# xmosio2.net
KiCad netlist of a schematic drawn in EAGLE
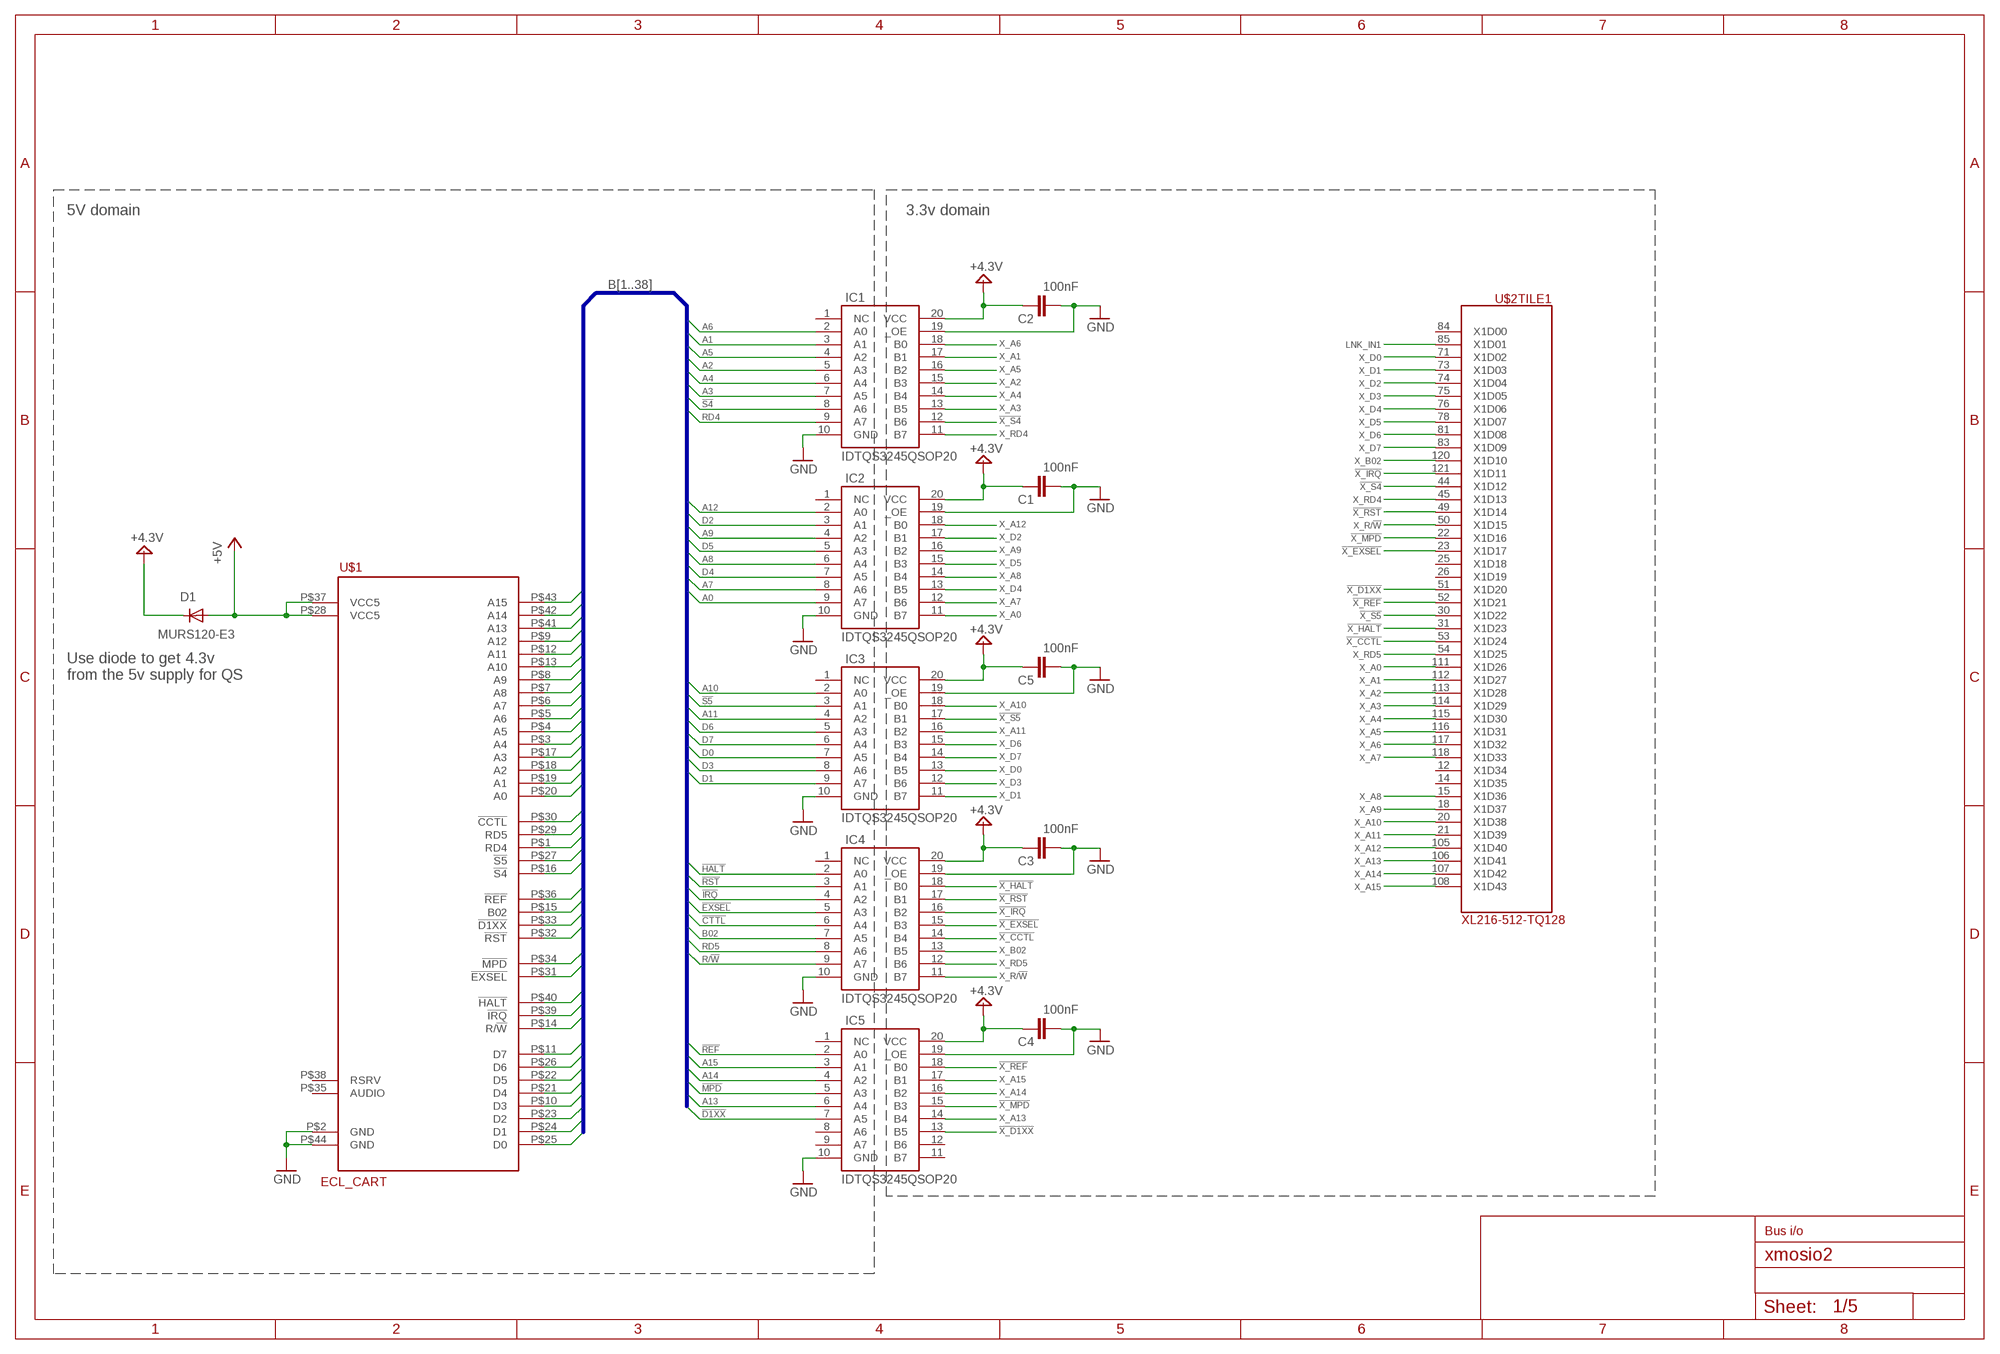
[diagram p0: schematic, sheet 1]
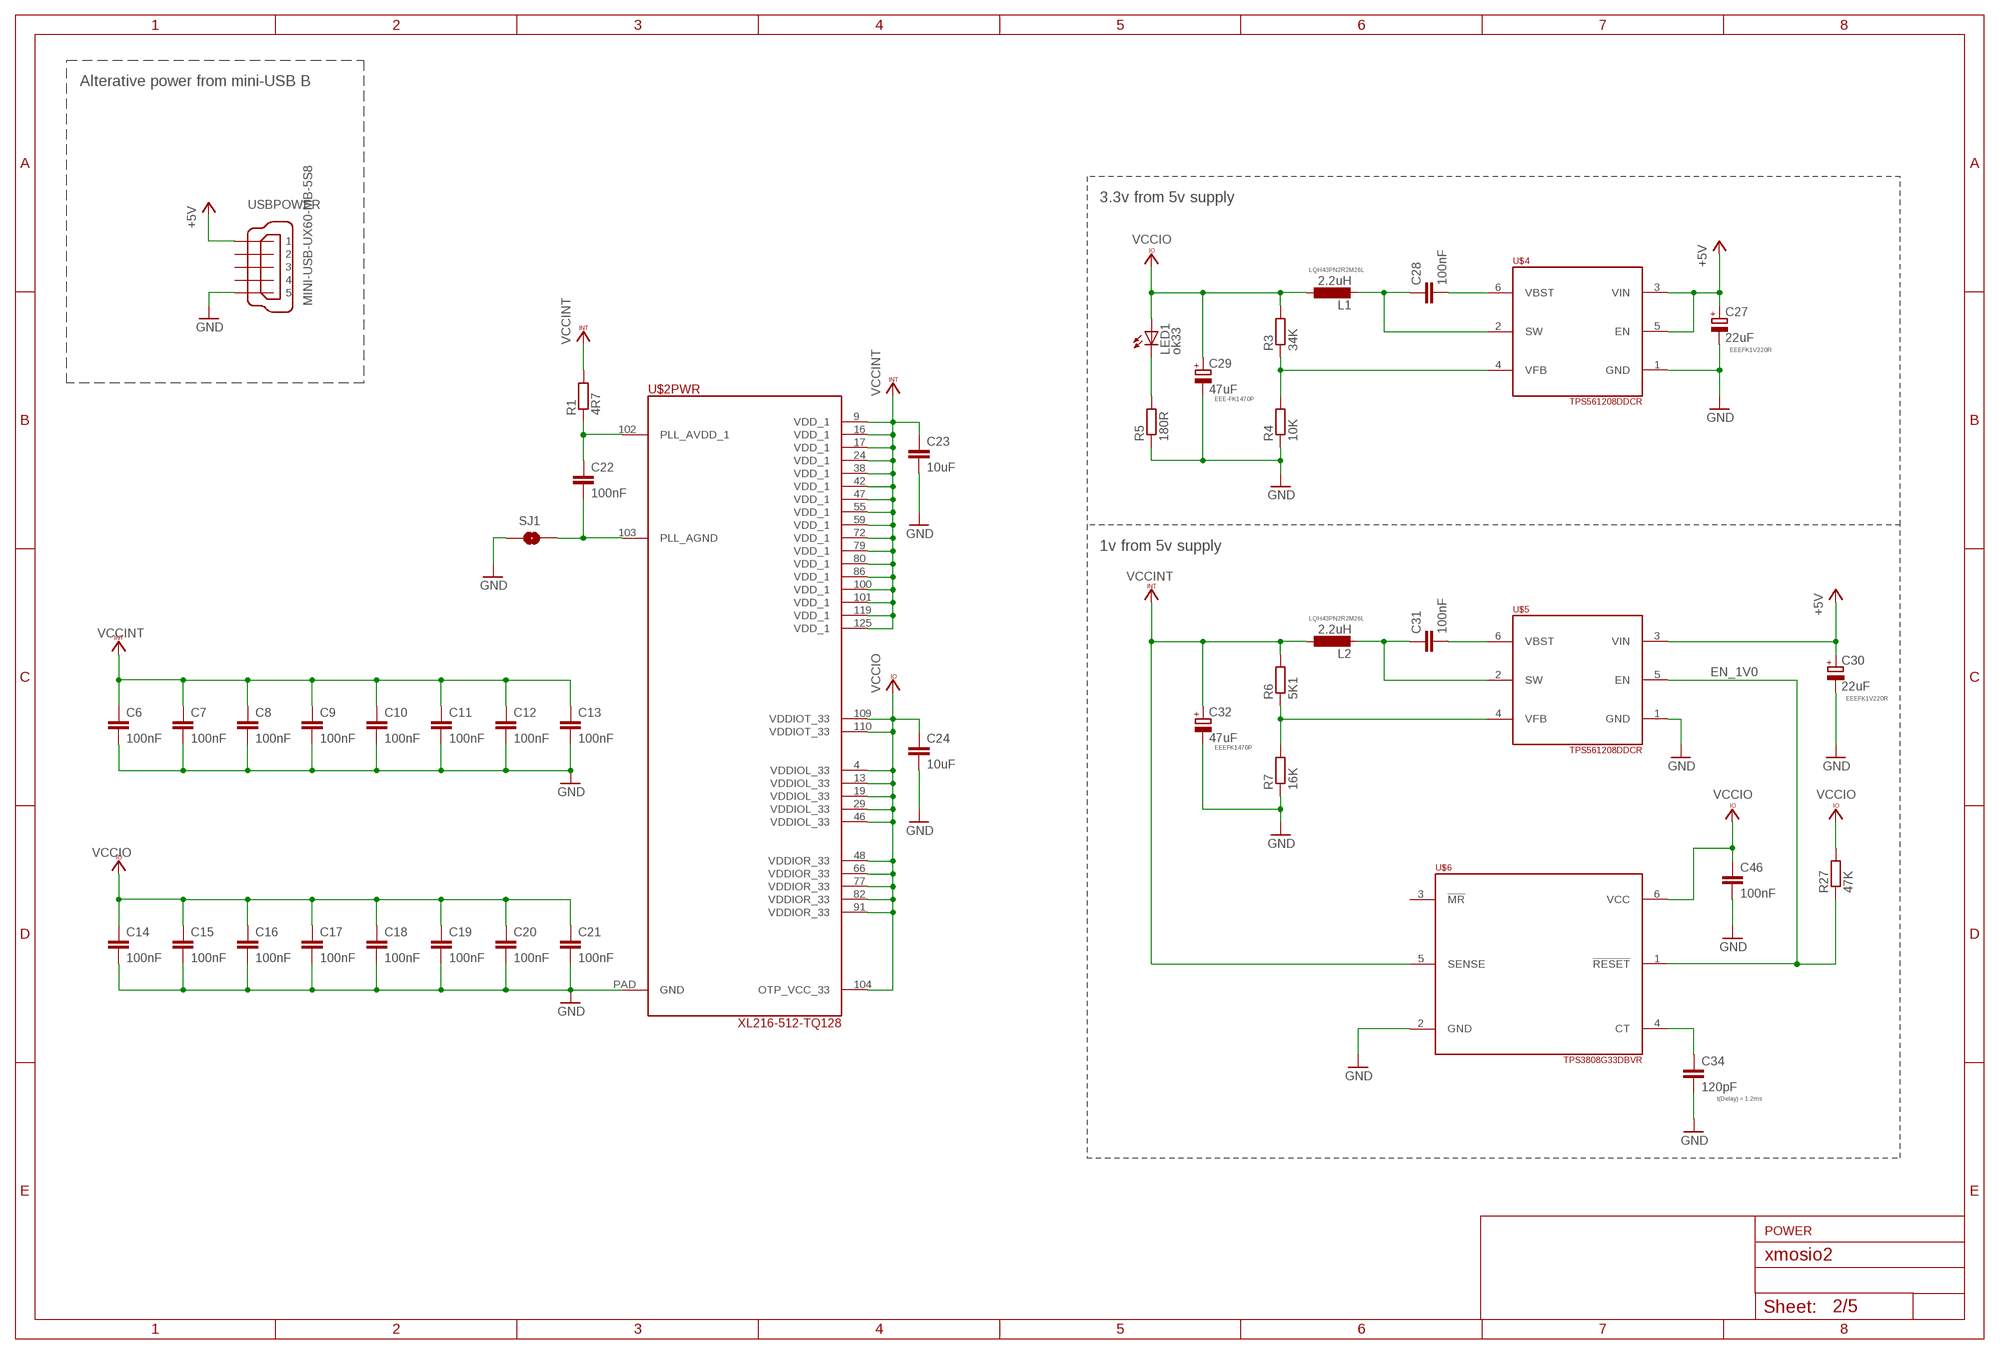
[diagram p1: schematic, sheet 2]
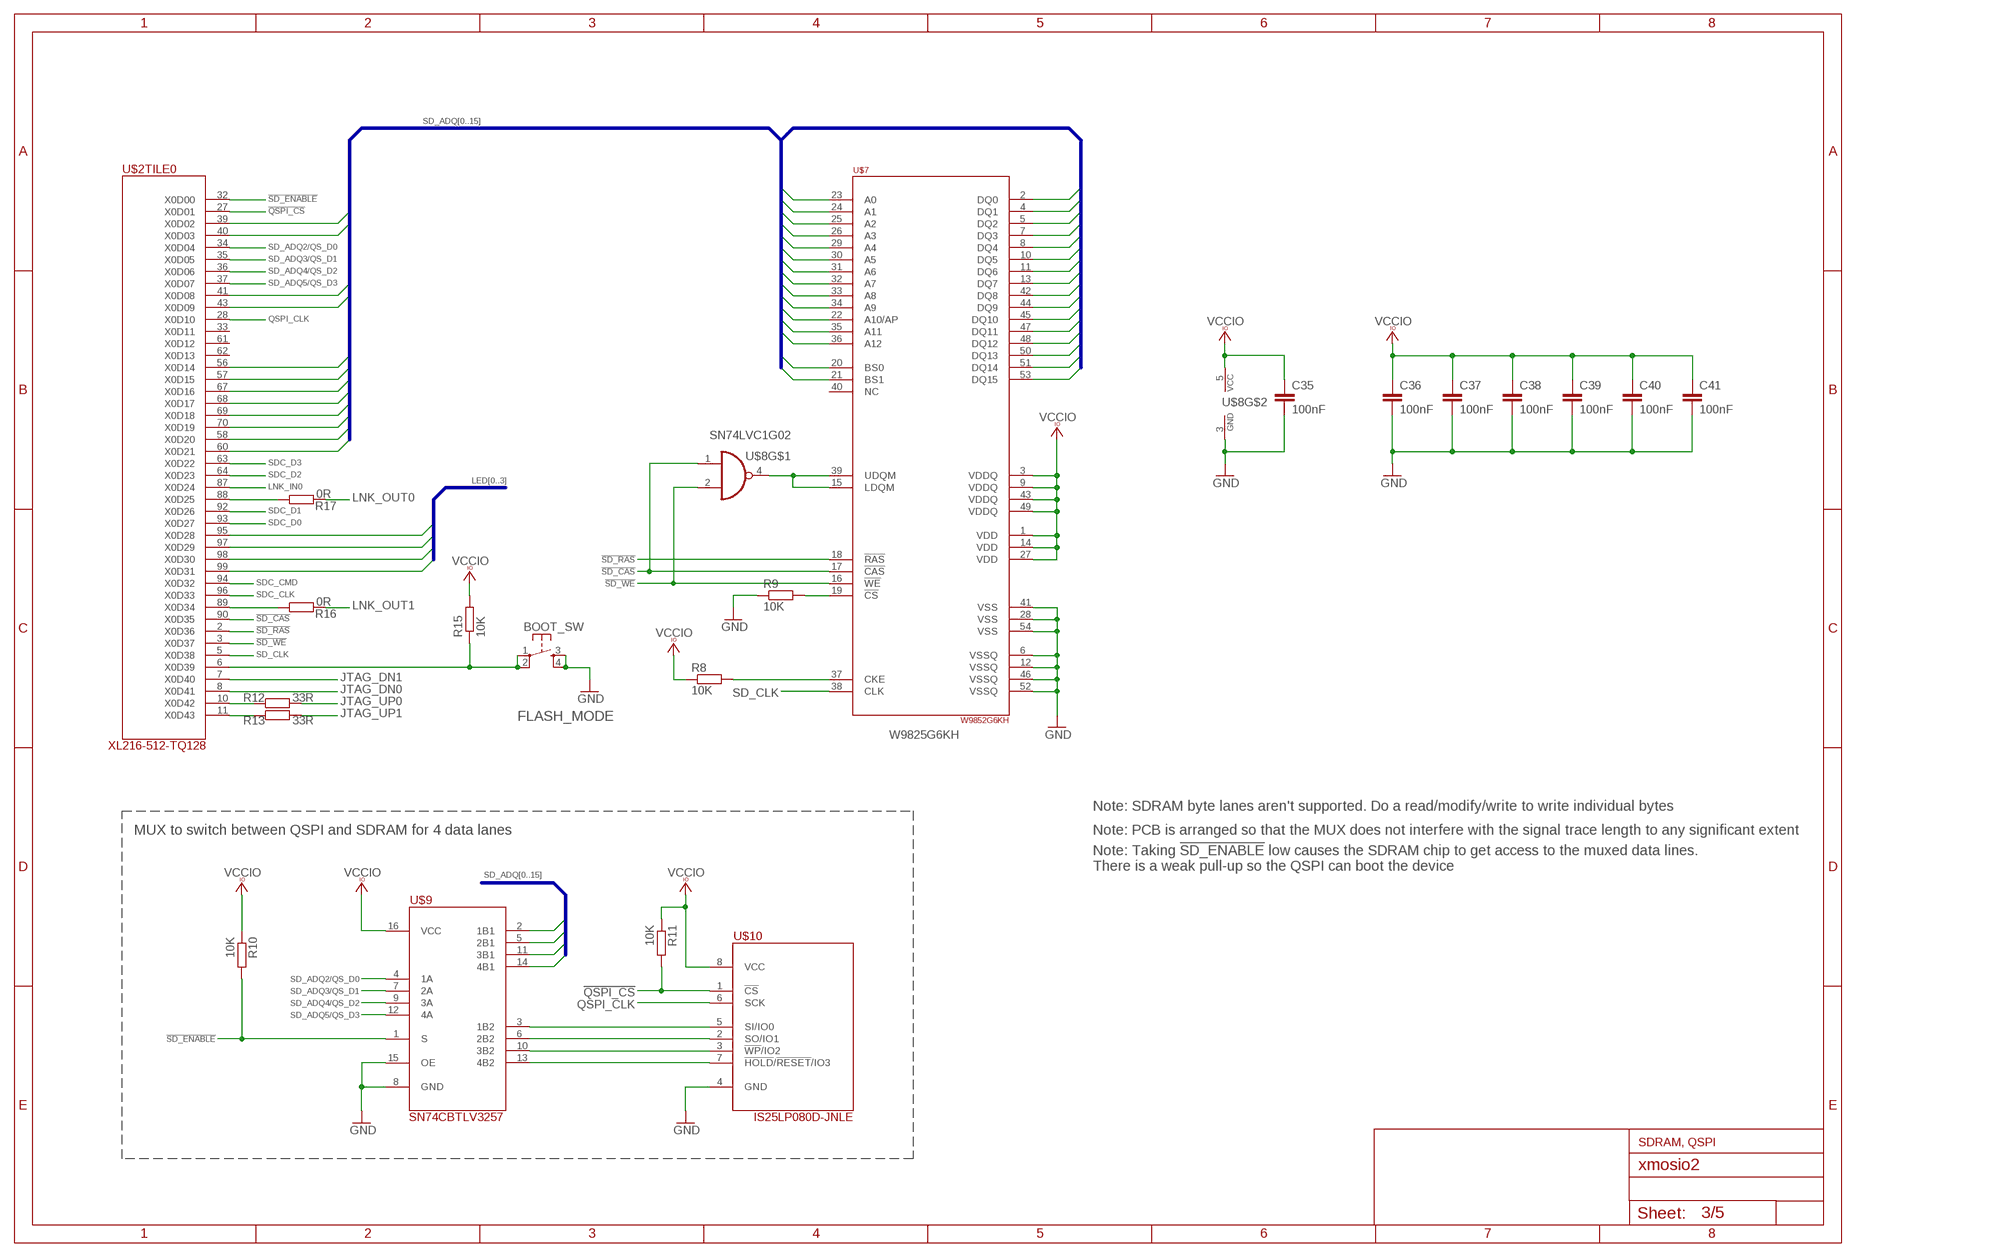
[diagram p2: schematic, sheet 3]
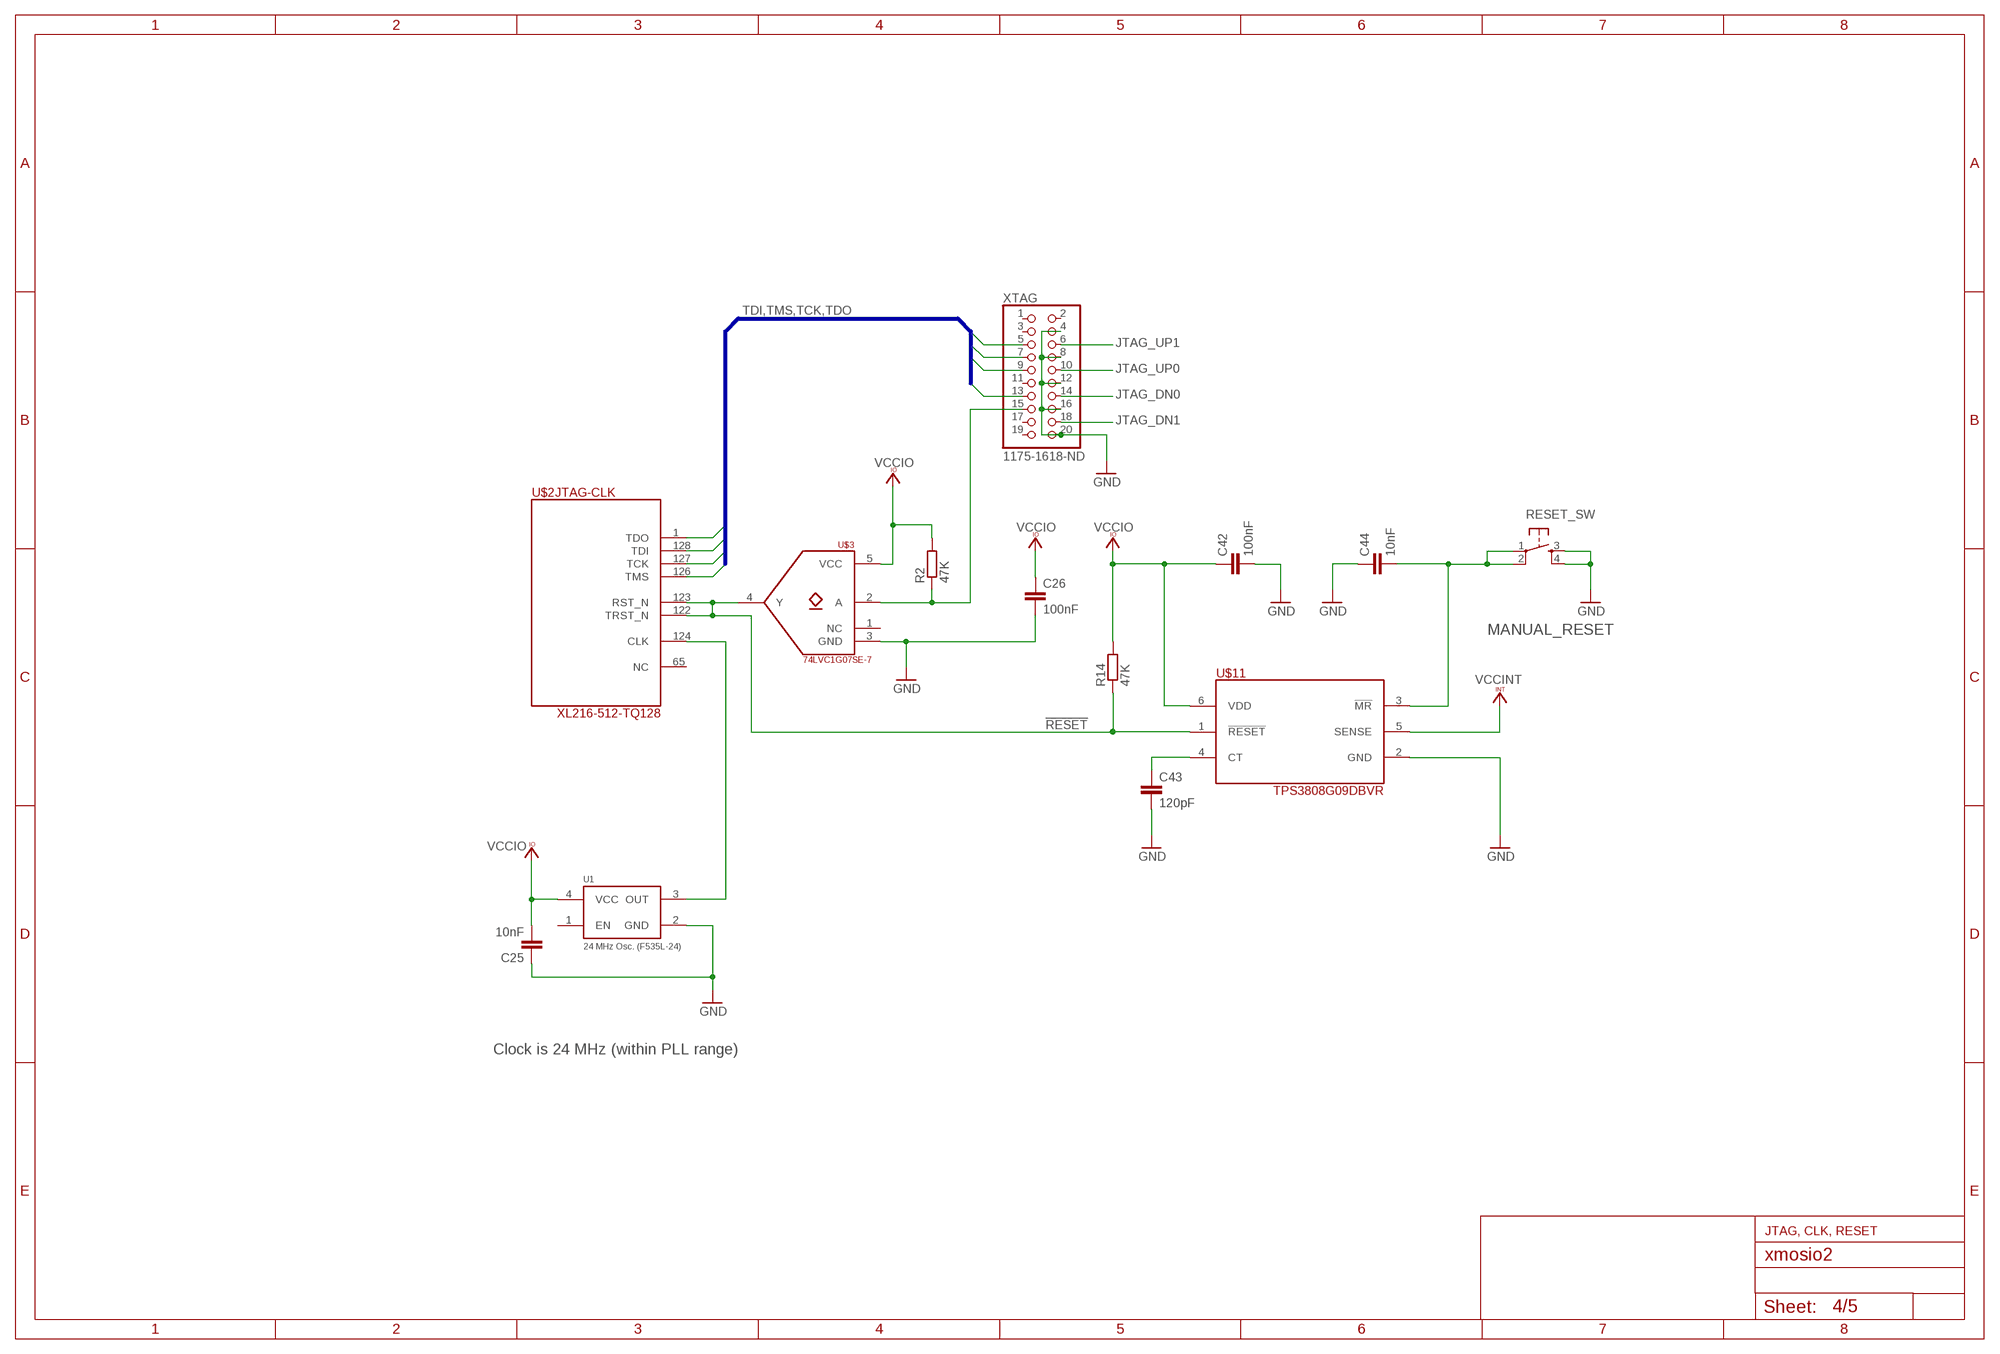
[diagram p3: schematic, sheet 4]
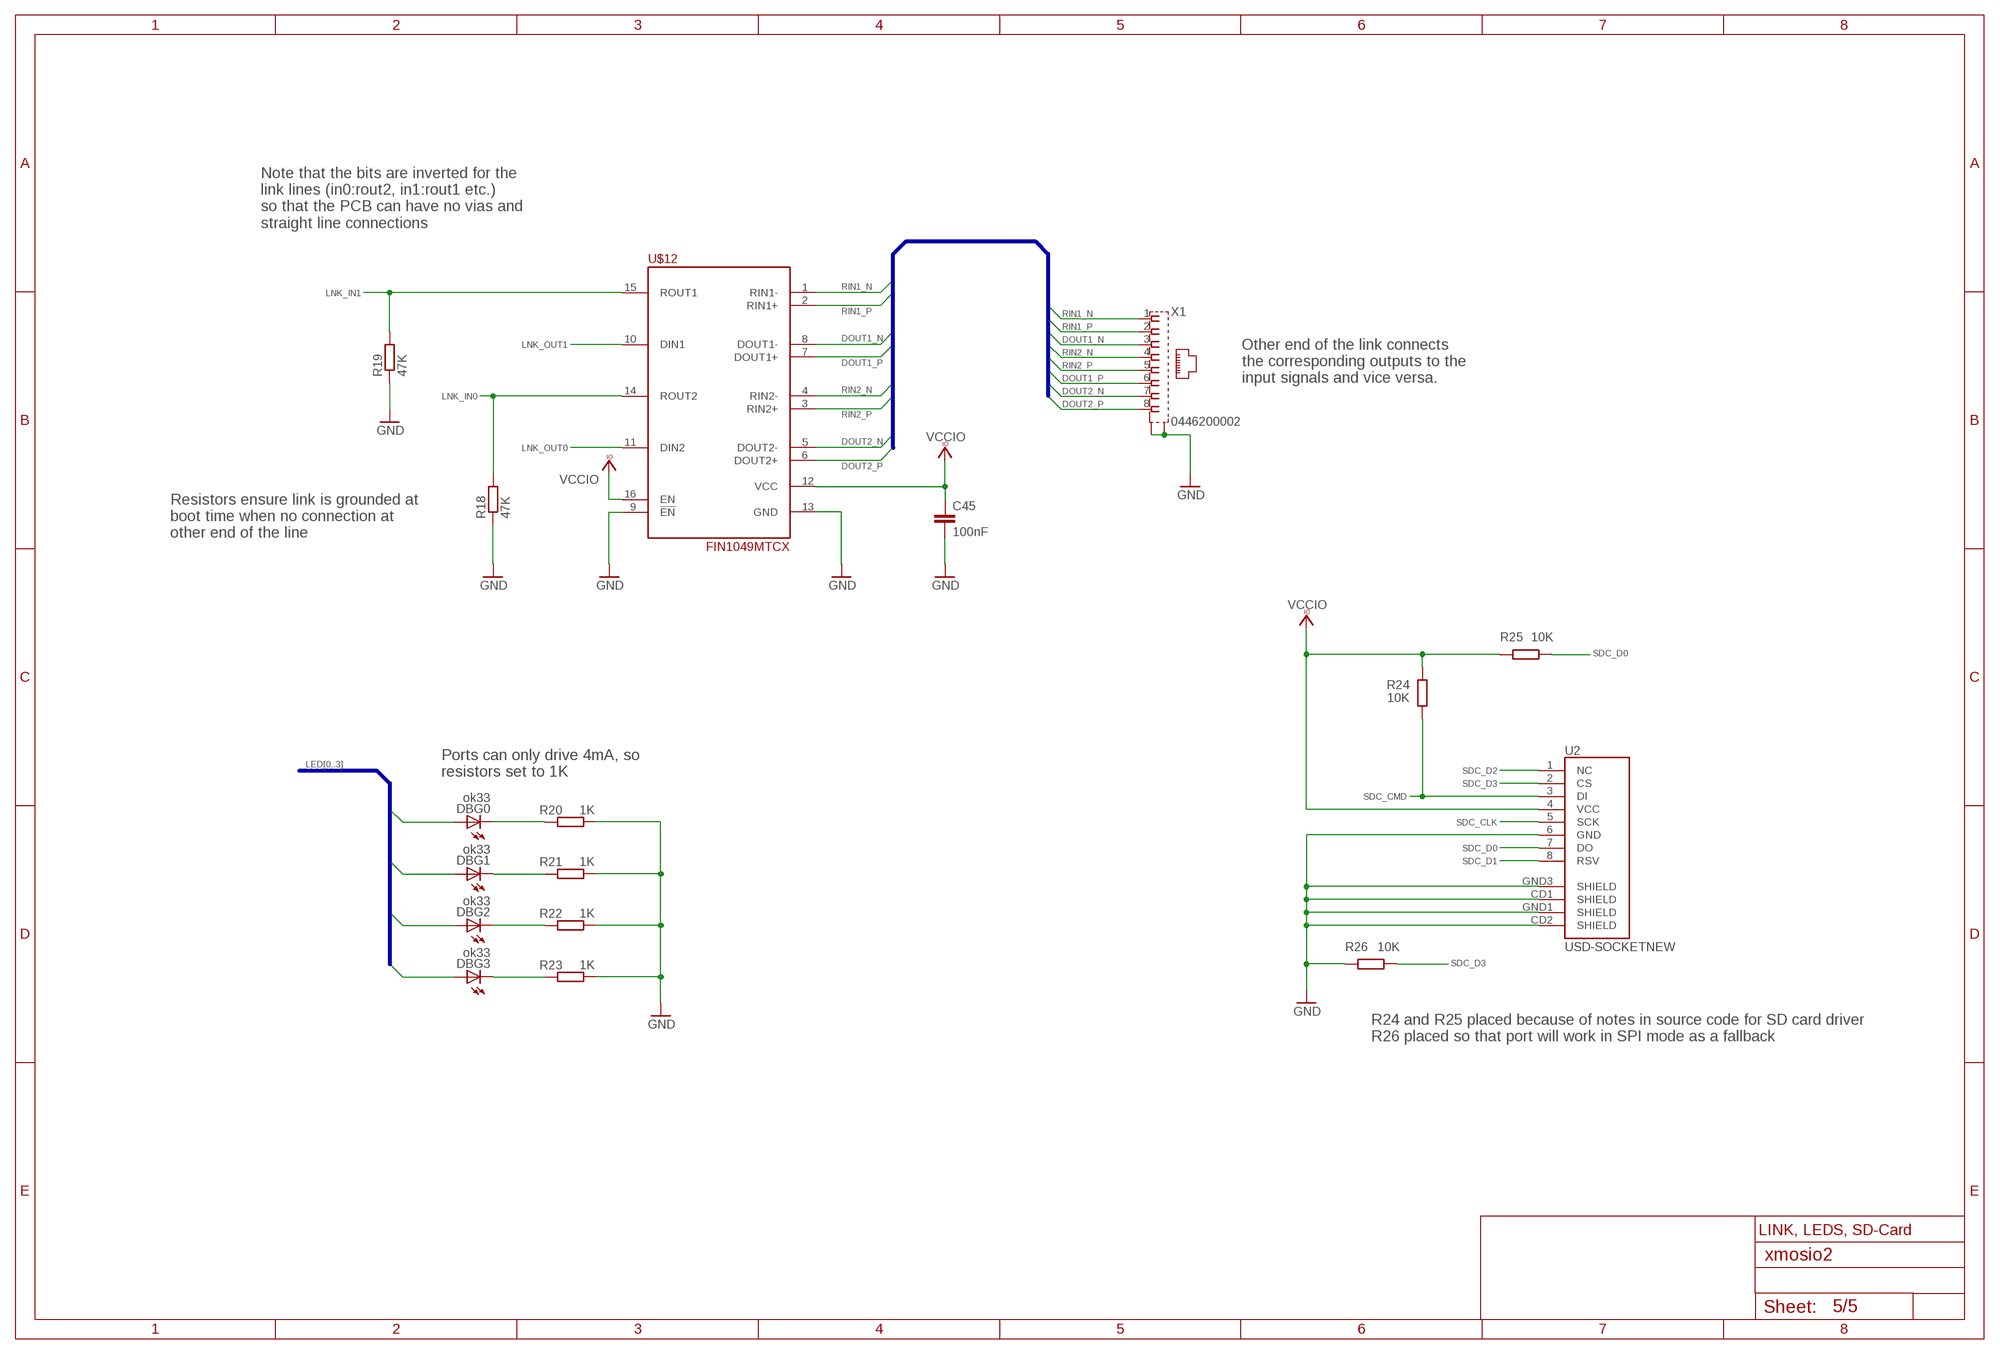
[diagram p4: schematic, sheet 5]

(export (version "E")
  (design (tool "Eeschema 10.0.6"))
  (components
    (comp (ref "C6")
      (value "100nF")
      (footprint "eagle-import:C0603")
      (libsource (lib "eagle-import") (part "C-EUC0603"))
    )
    (comp (ref "C7")
      (value "100nF")
      (footprint "eagle-import:C0603")
      (libsource (lib "eagle-import") (part "C-EUC0603"))
    )
    (comp (ref "C8")
      (value "100nF")
      (footprint "eagle-import:C0603")
      (libsource (lib "eagle-import") (part "C-EUC0603"))
    )
    (comp (ref "C9")
      (value "100nF")
      (footprint "eagle-import:C0603")
      (libsource (lib "eagle-import") (part "C-EUC0603"))
    )
    (comp (ref "C10")
      (value "100nF")
      (footprint "eagle-import:C0603")
      (libsource (lib "eagle-import") (part "C-EUC0603"))
    )
    (comp (ref "C11")
      (value "100nF")
      (footprint "eagle-import:C0603")
      (libsource (lib "eagle-import") (part "C-EUC0603"))
    )
    (comp (ref "C12")
      (value "100nF")
      (footprint "eagle-import:C0603")
      (libsource (lib "eagle-import") (part "C-EUC0603"))
    )
    (comp (ref "C13")
      (value "100nF")
      (footprint "eagle-import:C0603")
      (libsource (lib "eagle-import") (part "C-EUC0603"))
    )
    (comp (ref "C14")
      (value "100nF")
      (footprint "eagle-import:C0603")
      (libsource (lib "eagle-import") (part "C-EUC0603"))
    )
    (comp (ref "C15")
      (value "100nF")
      (footprint "eagle-import:C0603")
      (libsource (lib "eagle-import") (part "C-EUC0603"))
    )
    (comp (ref "C16")
      (value "100nF")
      (footprint "eagle-import:C0603")
      (libsource (lib "eagle-import") (part "C-EUC0603"))
    )
    (comp (ref "C17")
      (value "100nF")
      (footprint "eagle-import:C0603")
      (libsource (lib "eagle-import") (part "C-EUC0603"))
    )
    (comp (ref "C18")
      (value "100nF")
      (footprint "eagle-import:C0603")
      (libsource (lib "eagle-import") (part "C-EUC0603"))
    )
    (comp (ref "C19")
      (value "100nF")
      (footprint "eagle-import:C0603")
      (libsource (lib "eagle-import") (part "C-EUC0603"))
    )
    (comp (ref "C20")
      (value "100nF")
      (footprint "eagle-import:C0603")
      (libsource (lib "eagle-import") (part "C-EUC0603"))
    )
    (comp (ref "C21")
      (value "100nF")
      (footprint "eagle-import:C0603")
      (libsource (lib "eagle-import") (part "C-EUC0603"))
    )
    (comp (ref "C22")
      (value "100nF")
      (footprint "eagle-import:C0603")
      (libsource (lib "eagle-import") (part "C-EUC0603"))
    )
    (comp (ref "C23")
      (value "10uF")
      (footprint "eagle-import:C0603")
      (libsource (lib "eagle-import") (part "C-EUC0603"))
    )
    (comp (ref "C24")
      (value "10uF")
      (footprint "eagle-import:C0603")
      (libsource (lib "eagle-import") (part "C-EUC0603"))
    )
    (comp (ref "C27")
      (value "22uF")
      (footprint "eagle-import:PANASONIC_C")
      (libsource (lib "eagle-import") (part "CPOL-EUC"))
    )
    (comp (ref "C28")
      (value "100nF")
      (footprint "eagle-import:C0603")
      (libsource (lib "eagle-import") (part "C-EUC0603"))
    )
    (comp (ref "C29")
      (value "47uF")
      (footprint "eagle-import:PANASONIC_D")
      (libsource (lib "eagle-import") (part "CPOL-EUD"))
    )
    (comp (ref "C30")
      (value "22uF")
      (footprint "eagle-import:PANASONIC_C")
      (libsource (lib "eagle-import") (part "CPOL-EUC"))
    )
    (comp (ref "C31")
      (value "100nF")
      (footprint "eagle-import:C0603")
      (libsource (lib "eagle-import") (part "C-EUC0603"))
    )
    (comp (ref "C32")
      (value "47uF")
      (footprint "eagle-import:PANASONIC_D")
      (libsource (lib "eagle-import") (part "CPOL-EUD"))
    )
    (comp (ref "C34")
      (value "120pF")
      (footprint "eagle-import:C0603")
      (libsource (lib "eagle-import") (part "C-EUC0603"))
    )
    (comp (ref "C46")
      (value "100nF")
      (footprint "eagle-import:C0603")
      (libsource (lib "eagle-import") (part "C-EUC0603"))
    )
    (comp (ref "L1")
      (value "2.2uH")
      (footprint "eagle-import:L1812")
      (libsource (lib "eagle-import") (part "L-EUL1812"))
    )
    (comp (ref "L2")
      (value "2.2uH")
      (footprint "eagle-import:L1812")
      (libsource (lib "eagle-import") (part "L-EUL1812"))
    )
    (comp (ref "LED1")
      (value "ok33")
      (footprint "eagle-import:CHIP-LED0805")
      (libsource (lib "eagle-import") (part "LEDCHIP-LED0805"))
    )
    (comp (ref "R1")
      (value "4R7")
      (footprint "eagle-import:R0603")
      (libsource (lib "eagle-import") (part "R-EU_R0603"))
    )
    (comp (ref "R3")
      (value "34K")
      (footprint "eagle-import:R0603")
      (libsource (lib "eagle-import") (part "R-EU_R0603"))
    )
    (comp (ref "R4")
      (value "10K")
      (footprint "eagle-import:R0603")
      (libsource (lib "eagle-import") (part "R-EU_R0603"))
    )
    (comp (ref "R5")
      (value "180R")
      (footprint "eagle-import:R0603")
      (libsource (lib "eagle-import") (part "R-EU_R0603"))
    )
    (comp (ref "R6")
      (value "5K1")
      (footprint "eagle-import:R0603")
      (libsource (lib "eagle-import") (part "R-EU_R0603"))
    )
    (comp (ref "R7")
      (value "16K")
      (footprint "eagle-import:R0603")
      (libsource (lib "eagle-import") (part "R-EU_R0603"))
    )
    (comp (ref "R27")
      (value "47K")
      (footprint "eagle-import:R0603")
      (libsource (lib "eagle-import") (part "R-EU_R0603"))
    )
    (comp (ref "SJ1")
      (value "SOLDERJUMPERNC")
      (footprint "eagle-import:SJ_2S")
      (libsource (lib "eagle-import") (part "SOLDERJUMPERNC"))
    )
    (comp (ref "U$2")
      (value "XL216-512-TQ128")
      (footprint "eagle-import:TQFP128")
      (libsource (lib "eagle-import") (part "XL216-512-TQ128"))
    )
    (comp (ref "U$4")
      (value "TPS561208DDCR")
      (footprint "eagle-import:TSOT23-6_DDC")
      (libsource (lib "eagle-import") (part "TPS561208DDCR"))
    )
    (comp (ref "U$5")
      (value "TPS561208DDCR")
      (footprint "eagle-import:TSOT23-6_DDC")
      (libsource (lib "eagle-import") (part "TPS561208DDCR"))
    )
    (comp (ref "U$6")
      (value "TPS3808G33DBVR")
      (footprint "eagle-import:SOT23-6")
      (libsource (lib "eagle-import") (part "TPS3808G33DBVR"))
    )
    (comp (ref "USBPOWER")
      (value "MINI-USB-UX60-MB-5S8")
      (footprint "eagle-import:UX60-MB-5S8")
      (libsource (lib "eagle-import") (part "MINI-USB-UX60-MB-5S8"))
    )
    (comp (ref "C25")
      (value "10nF")
      (footprint "eagle-import:C0603")
      (libsource (lib "eagle-import") (part "C-EUC0603"))
    )
    (comp (ref "C26")
      (value "100nF")
      (footprint "eagle-import:C0603")
      (libsource (lib "eagle-import") (part "C-EUC0603"))
    )
    (comp (ref "C42")
      (value "100nF")
      (footprint "eagle-import:C0603")
      (libsource (lib "eagle-import") (part "C-EUC0603"))
    )
    (comp (ref "C43")
      (value "120pF")
      (footprint "eagle-import:C0603")
      (libsource (lib "eagle-import") (part "C-EUC0603"))
    )
    (comp (ref "C44")
      (value "10nF")
      (footprint "eagle-import:C0603")
      (libsource (lib "eagle-import") (part "C-EUC0603"))
    )
    (comp (ref "R2")
      (value "47K")
      (footprint "eagle-import:R0603")
      (libsource (lib "eagle-import") (part "R-EU_R0603"))
    )
    (comp (ref "R14")
      (value "47K")
      (footprint "eagle-import:R0603")
      (libsource (lib "eagle-import") (part "R-EU_R0603"))
    )
    (comp (ref "RESET_SW")
      (value "MANUAL_RESET")
      (footprint "eagle-import:TACTILE-PTH")
      (libsource (lib "eagle-import") (part "TAC_SWITCHPTH"))
    )
    (comp (ref "U$3")
      (value "74LVC1G07SE-7")
      (footprint "eagle-import:SOT23-5")
      (libsource (lib "eagle-import") (part "74LVC1G07SE-7"))
    )
    (comp (ref "U$11")
      (value "TPS3808G09DBVR")
      (footprint "eagle-import:SOT23-6")
      (libsource (lib "eagle-import") (part "TPS3808G09DBVR"))
    )
    (comp (ref "U1")
      (value "24 MHz Osc. (F535L-24)")
      (footprint "eagle-import:CRYSTAL-OSC-SMD-5X3")
      (libsource (lib "eagle-import") (part "OSCILLATOR5X3-PIN1-INDICATED"))
    )
    (comp (ref "XTAG")
      (value "1175-1618-ND")
      (footprint "eagle-import:2X10_90")
      (libsource (lib "eagle-import") (part "PINHD-2X10/90"))
    )
    (comp (ref "C1")
      (value "100nF")
      (footprint "eagle-import:C0603")
      (libsource (lib "eagle-import") (part "C-EUC0603"))
    )
    (comp (ref "C2")
      (value "100nF")
      (footprint "eagle-import:C0603")
      (libsource (lib "eagle-import") (part "C-EUC0603"))
    )
    (comp (ref "C3")
      (value "100nF")
      (footprint "eagle-import:C0603")
      (libsource (lib "eagle-import") (part "C-EUC0603"))
    )
    (comp (ref "C4")
      (value "100nF")
      (footprint "eagle-import:C0603")
      (libsource (lib "eagle-import") (part "C-EUC0603"))
    )
    (comp (ref "C5")
      (value "100nF")
      (footprint "eagle-import:C0603")
      (libsource (lib "eagle-import") (part "C-EUC0603"))
    )
    (comp (ref "D1")
      (value "MURS120-E3")
      (footprint "eagle-import:SMB")
      (libsource (lib "eagle-import") (part "DIODE-SMB"))
    )
    (comp (ref "IC1")
      (value "IDTQS3245QSOP20")
      (footprint "eagle-import:QSOP20")
      (libsource (lib "eagle-import") (part "IDTQS3245QSOP20"))
    )
    (comp (ref "IC2")
      (value "IDTQS3245QSOP20")
      (footprint "eagle-import:QSOP20")
      (libsource (lib "eagle-import") (part "IDTQS3245QSOP20"))
    )
    (comp (ref "IC3")
      (value "IDTQS3245QSOP20")
      (footprint "eagle-import:QSOP20")
      (libsource (lib "eagle-import") (part "IDTQS3245QSOP20"))
    )
    (comp (ref "IC4")
      (value "IDTQS3245QSOP20")
      (footprint "eagle-import:QSOP20")
      (libsource (lib "eagle-import") (part "IDTQS3245QSOP20"))
    )
    (comp (ref "IC5")
      (value "IDTQS3245QSOP20")
      (footprint "eagle-import:QSOP20")
      (libsource (lib "eagle-import") (part "IDTQS3245QSOP20"))
    )
    (comp (ref "U$1")
      (value "ECL_CART")
      (footprint "eagle-import:ECL_CART")
      (libsource (lib "eagle-import") (part "ECL_CART"))
    )
    (comp (ref "C45")
      (value "100nF")
      (footprint "eagle-import:C0603")
      (libsource (lib "eagle-import") (part "C-EUC0603"))
    )
    (comp (ref "DBG0")
      (value "ok33")
      (footprint "eagle-import:CHIP-LED0805")
      (libsource (lib "eagle-import") (part "LEDCHIP-LED0805"))
    )
    (comp (ref "DBG1")
      (value "ok33")
      (footprint "eagle-import:CHIP-LED0805")
      (libsource (lib "eagle-import") (part "LEDCHIP-LED0805"))
    )
    (comp (ref "DBG2")
      (value "ok33")
      (footprint "eagle-import:CHIP-LED0805")
      (libsource (lib "eagle-import") (part "LEDCHIP-LED0805"))
    )
    (comp (ref "DBG3")
      (value "ok33")
      (footprint "eagle-import:CHIP-LED0805")
      (libsource (lib "eagle-import") (part "LEDCHIP-LED0805"))
    )
    (comp (ref "R18")
      (value "47K")
      (footprint "eagle-import:R0603")
      (libsource (lib "eagle-import") (part "R-EU_R0603"))
    )
    (comp (ref "R19")
      (value "47K")
      (footprint "eagle-import:R0603")
      (libsource (lib "eagle-import") (part "R-EU_R0603"))
    )
    (comp (ref "R20")
      (value "1K")
      (footprint "eagle-import:R0603")
      (libsource (lib "eagle-import") (part "R-EU_R0603"))
    )
    (comp (ref "R21")
      (value "1K")
      (footprint "eagle-import:R0603")
      (libsource (lib "eagle-import") (part "R-EU_R0603"))
    )
    (comp (ref "R22")
      (value "1K")
      (footprint "eagle-import:R0603")
      (libsource (lib "eagle-import") (part "R-EU_R0603"))
    )
    (comp (ref "R23")
      (value "1K")
      (footprint "eagle-import:R0603")
      (libsource (lib "eagle-import") (part "R-EU_R0603"))
    )
    (comp (ref "R24")
      (value "10K")
      (footprint "eagle-import:R0603")
      (libsource (lib "eagle-import") (part "R-EU_R0603"))
    )
    (comp (ref "R25")
      (value "10K")
      (footprint "eagle-import:R0603")
      (libsource (lib "eagle-import") (part "R-EU_R0603"))
    )
    (comp (ref "R26")
      (value "10K")
      (footprint "eagle-import:R0603")
      (libsource (lib "eagle-import") (part "R-EU_R0603"))
    )
    (comp (ref "U$12")
      (value "FIN1049MTCX")
      (footprint "eagle-import:TSSOP16")
      (libsource (lib "eagle-import") (part "FIN1049MTCX"))
    )
    (comp (ref "U2")
      (value "USD-SOCKETNEW")
      (footprint "eagle-import:MICRO-SD-SOCKET-PP")
      (libsource (lib "eagle-import") (part "USD-SOCKETNEW"))
    )
    (comp (ref "X1")
      (value "0446200002")
      (footprint "eagle-import:0446200002")
      (fields (field (name "MF") "MOLEX"))
      (libsource (lib "eagle-import") (part "0446200002"))
    )
    (comp (ref "BOOT_SW")
      (value "FLASH_MODE")
      (footprint "eagle-import:TACTILE-PTH")
      (libsource (lib "eagle-import") (part "TAC_SWITCHPTH"))
    )
    (comp (ref "C35")
      (value "100nF")
      (footprint "eagle-import:C0603")
      (libsource (lib "eagle-import") (part "C-EUC0603"))
    )
    (comp (ref "C36")
      (value "100nF")
      (footprint "eagle-import:C0603")
      (libsource (lib "eagle-import") (part "C-EUC0603"))
    )
    (comp (ref "C37")
      (value "100nF")
      (footprint "eagle-import:C0603")
      (libsource (lib "eagle-import") (part "C-EUC0603"))
    )
    (comp (ref "C38")
      (value "100nF")
      (footprint "eagle-import:C0603")
      (libsource (lib "eagle-import") (part "C-EUC0603"))
    )
    (comp (ref "C39")
      (value "100nF")
      (footprint "eagle-import:C0603")
      (libsource (lib "eagle-import") (part "C-EUC0603"))
    )
    (comp (ref "C40")
      (value "100nF")
      (footprint "eagle-import:C0603")
      (libsource (lib "eagle-import") (part "C-EUC0603"))
    )
    (comp (ref "C41")
      (value "100nF")
      (footprint "eagle-import:C0603")
      (libsource (lib "eagle-import") (part "C-EUC0603"))
    )
    (comp (ref "R8")
      (value "10K")
      (footprint "eagle-import:R0603")
      (libsource (lib "eagle-import") (part "R-EU_R0603"))
    )
    (comp (ref "R9")
      (value "10K")
      (footprint "eagle-import:R0603")
      (libsource (lib "eagle-import") (part "R-EU_R0603"))
    )
    (comp (ref "R10")
      (value "10K")
      (footprint "eagle-import:R0603")
      (libsource (lib "eagle-import") (part "R-EU_R0603"))
    )
    (comp (ref "R11")
      (value "10K")
      (footprint "eagle-import:R0603")
      (libsource (lib "eagle-import") (part "R-EU_R0603"))
    )
    (comp (ref "R12")
      (value "33R")
      (footprint "eagle-import:R0603")
      (libsource (lib "eagle-import") (part "R-EU_R0603"))
    )
    (comp (ref "R13")
      (value "33R")
      (footprint "eagle-import:R0603")
      (libsource (lib "eagle-import") (part "R-EU_R0603"))
    )
    (comp (ref "R15")
      (value "10K")
      (footprint "eagle-import:R0603")
      (libsource (lib "eagle-import") (part "R-EU_R0603"))
    )
    (comp (ref "R16")
      (value "0R")
      (footprint "eagle-import:R0603")
      (libsource (lib "eagle-import") (part "R-EU_R0603"))
    )
    (comp (ref "R17")
      (value "0R")
      (footprint "eagle-import:R0603")
      (libsource (lib "eagle-import") (part "R-EU_R0603"))
    )
    (comp (ref "U$7")
      (value "W9852G6KH")
      (footprint "eagle-import:TSOP54-400")
      (libsource (lib "eagle-import") (part "W9852G6KH"))
    )
    (comp (ref "U$8")
      (value "SN74LVC1G02")
      (footprint "eagle-import:SOT23-5")
      (libsource (lib "eagle-import") (part "SN74LVC1G02"))
    )
    (comp (ref "U$9")
      (value "SN74CBTLV3257")
      (footprint "eagle-import:SO16")
      (libsource (lib "eagle-import") (part "SN74CBTLV3257"))
    )
    (comp (ref "U$10")
      (value "IS25LP080D-JNLE")
      (footprint "eagle-import:SO-08")
      (libsource (lib "eagle-import") (part "IS25LP080D-JNLE"))
    )
  )
  (nets
    (net (code "1") (name "+4.3V") (class "Default")
      (node (ref "C1") (pin "1") (pinfunction "1_1") (pintype "passive"))
      (node (ref "C2") (pin "1") (pinfunction "1_1") (pintype "passive"))
      (node (ref "C3") (pin "1") (pinfunction "1_1") (pintype "passive"))
      (node (ref "C4") (pin "1") (pinfunction "1_1") (pintype "passive"))
      (node (ref "C5") (pin "1") (pinfunction "1_1") (pintype "passive"))
      (node (ref "D1") (pin "C") (pinfunction "C_C") (pintype "passive"))
      (node (ref "IC1") (pin "20") (pinfunction "VCC_20") (pintype "power_in"))
      (node (ref "IC2") (pin "20") (pinfunction "VCC_20") (pintype "power_in"))
      (node (ref "IC3") (pin "20") (pinfunction "VCC_20") (pintype "power_in"))
      (node (ref "IC4") (pin "20") (pinfunction "VCC_20") (pintype "power_in"))
      (node (ref "IC5") (pin "20") (pinfunction "VCC_20") (pintype "power_in"))
    )
    (net (code "2") (name "+5V") (class "Default")
      (node (ref "C27") (pin "+") (pinfunction "+_+") (pintype "passive"))
      (node (ref "C30") (pin "+") (pinfunction "+_+") (pintype "passive"))
      (node (ref "D1") (pin "A") (pinfunction "A_A") (pintype "passive"))
      (node (ref "U$1") (pin "P$28") (pinfunction "VCC5_P$28") (pintype "bidirectional"))
      (node (ref "U$1") (pin "P$37") (pinfunction "VCC5_P$37") (pintype "bidirectional"))
      (node (ref "U$4") (pin "3") (pinfunction "VIN_3") (pintype "bidirectional"))
      (node (ref "U$4") (pin "5") (pinfunction "EN_5") (pintype "bidirectional"))
      (node (ref "U$5") (pin "3") (pinfunction "VIN_3") (pintype "bidirectional"))
      (node (ref "USBPOWER") (pin "1") (pinfunction "1_1") (pintype "input"))
    )
    (net (code "8") (name "B1") (class "Default")
      (node (ref "IC1") (pin "9") (pinfunction "A7_9") (pintype "bidirectional"))
      (node (ref "U$1") (pin "P$1") (pinfunction "RD4_P$1") (pintype "bidirectional"))
    )
    (net (code "9") (name "B2") (class "Default")
      (node (ref "IC1") (pin "8") (pinfunction "A6_8") (pintype "bidirectional"))
      (node (ref "U$1") (pin "P$16") (pinfunction "~{S4}_P$16") (pintype "bidirectional"))
    )
    (net (code "10") (name "B3") (class "Default")
      (node (ref "IC1") (pin "7") (pinfunction "A5_7") (pintype "bidirectional"))
      (node (ref "U$1") (pin "P$17") (pinfunction "A3_P$17") (pintype "bidirectional"))
    )
    (net (code "11") (name "B4") (class "Default")
      (node (ref "IC1") (pin "6") (pinfunction "A4_6") (pintype "bidirectional"))
      (node (ref "U$1") (pin "P$3") (pinfunction "A4_P$3") (pintype "bidirectional"))
    )
    (net (code "12") (name "B5") (class "Default")
      (node (ref "IC1") (pin "5") (pinfunction "A3_5") (pintype "bidirectional"))
      (node (ref "U$1") (pin "P$18") (pinfunction "A2_P$18") (pintype "bidirectional"))
    )
    (net (code "13") (name "B6") (class "Default")
      (node (ref "IC1") (pin "4") (pinfunction "A2_4") (pintype "bidirectional"))
      (node (ref "U$1") (pin "P$4") (pinfunction "A5_P$4") (pintype "bidirectional"))
    )
    (net (code "14") (name "B7") (class "Default")
      (node (ref "IC1") (pin "3") (pinfunction "A1_3") (pintype "bidirectional"))
      (node (ref "U$1") (pin "P$19") (pinfunction "A1_P$19") (pintype "bidirectional"))
    )
    (net (code "15") (name "B8") (class "Default")
      (node (ref "IC1") (pin "2") (pinfunction "A0_2") (pintype "bidirectional"))
      (node (ref "U$1") (pin "P$5") (pinfunction "A6_P$5") (pintype "bidirectional"))
    )
    (net (code "16") (name "B9") (class "Default")
      (node (ref "IC2") (pin "9") (pinfunction "A7_9") (pintype "bidirectional"))
      (node (ref "U$1") (pin "P$20") (pinfunction "A0_P$20") (pintype "bidirectional"))
    )
    (net (code "17") (name "B10") (class "Default")
      (node (ref "IC2") (pin "8") (pinfunction "A6_8") (pintype "bidirectional"))
      (node (ref "U$1") (pin "P$6") (pinfunction "A7_P$6") (pintype "bidirectional"))
    )
    (net (code "18") (name "B11") (class "Default")
      (node (ref "IC2") (pin "7") (pinfunction "A5_7") (pintype "bidirectional"))
      (node (ref "U$1") (pin "P$21") (pinfunction "D4_P$21") (pintype "bidirectional"))
    )
    (net (code "19") (name "B12") (class "Default")
      (node (ref "IC2") (pin "6") (pinfunction "A4_6") (pintype "bidirectional"))
      (node (ref "U$1") (pin "P$7") (pinfunction "A8_P$7") (pintype "bidirectional"))
    )
    (net (code "20") (name "B13") (class "Default")
      (node (ref "IC2") (pin "5") (pinfunction "A3_5") (pintype "bidirectional"))
      (node (ref "U$1") (pin "P$22") (pinfunction "D5_P$22") (pintype "bidirectional"))
    )
    (net (code "21") (name "B14") (class "Default")
      (node (ref "IC2") (pin "4") (pinfunction "A2_4") (pintype "bidirectional"))
      (node (ref "U$1") (pin "P$8") (pinfunction "A9_P$8") (pintype "bidirectional"))
    )
    (net (code "22") (name "B15") (class "Default")
      (node (ref "IC2") (pin "3") (pinfunction "A1_3") (pintype "bidirectional"))
      (node (ref "U$1") (pin "P$23") (pinfunction "D2_P$23") (pintype "bidirectional"))
    )
    (net (code "23") (name "B16") (class "Default")
      (node (ref "IC2") (pin "2") (pinfunction "A0_2") (pintype "bidirectional"))
      (node (ref "U$1") (pin "P$9") (pinfunction "A12_P$9") (pintype "bidirectional"))
    )
    (net (code "24") (name "B17") (class "Default")
      (node (ref "IC3") (pin "9") (pinfunction "A7_9") (pintype "bidirectional"))
      (node (ref "U$1") (pin "P$24") (pinfunction "D1_P$24") (pintype "bidirectional"))
    )
    (net (code "25") (name "B18") (class "Default")
      (node (ref "IC3") (pin "8") (pinfunction "A6_8") (pintype "bidirectional"))
      (node (ref "U$1") (pin "P$10") (pinfunction "D3_P$10") (pintype "bidirectional"))
    )
    (net (code "26") (name "B19") (class "Default")
      (node (ref "IC3") (pin "7") (pinfunction "A5_7") (pintype "bidirectional"))
      (node (ref "U$1") (pin "P$25") (pinfunction "D0_P$25") (pintype "bidirectional"))
    )
    (net (code "27") (name "B20") (class "Default")
      (node (ref "IC3") (pin "6") (pinfunction "A4_6") (pintype "bidirectional"))
      (node (ref "U$1") (pin "P$11") (pinfunction "D7_P$11") (pintype "bidirectional"))
    )
    (net (code "28") (name "B21") (class "Default")
      (node (ref "IC3") (pin "5") (pinfunction "A3_5") (pintype "bidirectional"))
      (node (ref "U$1") (pin "P$26") (pinfunction "D6_P$26") (pintype "bidirectional"))
    )
    (net (code "29") (name "B22") (class "Default")
      (node (ref "IC3") (pin "4") (pinfunction "A2_4") (pintype "bidirectional"))
      (node (ref "U$1") (pin "P$12") (pinfunction "A11_P$12") (pintype "bidirectional"))
    )
    (net (code "30") (name "B23") (class "Default")
      (node (ref "IC3") (pin "3") (pinfunction "A1_3") (pintype "bidirectional"))
      (node (ref "U$1") (pin "P$27") (pinfunction "~{S5}_P$27") (pintype "bidirectional"))
    )
    (net (code "31") (name "B24") (class "Default")
      (node (ref "IC3") (pin "2") (pinfunction "A0_2") (pintype "bidirectional"))
      (node (ref "U$1") (pin "P$13") (pinfunction "A10_P$13") (pintype "bidirectional"))
    )
    (net (code "32") (name "B25") (class "Default")
      (node (ref "IC4") (pin "9") (pinfunction "A7_9") (pintype "bidirectional"))
      (node (ref "U$1") (pin "P$14") (pinfunction "R/~{W}_P$14") (pintype "bidirectional"))
    )
    (net (code "33") (name "B26") (class "Default")
      (node (ref "IC4") (pin "8") (pinfunction "A6_8") (pintype "bidirectional"))
      (node (ref "U$1") (pin "P$29") (pinfunction "RD5_P$29") (pintype "bidirectional"))
    )
    (net (code "34") (name "B27") (class "Default")
      (node (ref "IC4") (pin "7") (pinfunction "A5_7") (pintype "bidirectional"))
      (node (ref "U$1") (pin "P$15") (pinfunction "B02_P$15") (pintype "bidirectional"))
    )
    (net (code "35") (name "B28") (class "Default")
      (node (ref "IC4") (pin "6") (pinfunction "A4_6") (pintype "bidirectional"))
      (node (ref "U$1") (pin "P$30") (pinfunction "~{CCTL}_P$30") (pintype "bidirectional"))
    )
    (net (code "36") (name "B29") (class "Default")
      (node (ref "IC4") (pin "5") (pinfunction "A3_5") (pintype "bidirectional"))
      (node (ref "U$1") (pin "P$31") (pinfunction "~{EXSEL}_P$31") (pintype "bidirectional"))
    )
    (net (code "37") (name "B30") (class "Default")
      (node (ref "IC4") (pin "4") (pinfunction "A2_4") (pintype "bidirectional"))
      (node (ref "U$1") (pin "P$39") (pinfunction "~{IRQ}_P$39") (pintype "bidirectional"))
    )
    (net (code "38") (name "B31") (class "Default")
      (node (ref "IC4") (pin "3") (pinfunction "A1_3") (pintype "bidirectional"))
      (node (ref "U$1") (pin "P$32") (pinfunction "~{RST}_P$32") (pintype "bidirectional"))
    )
    (net (code "39") (name "B32") (class "Default")
      (node (ref "IC4") (pin "2") (pinfunction "A0_2") (pintype "bidirectional"))
      (node (ref "U$1") (pin "P$40") (pinfunction "~{HALT}_P$40") (pintype "bidirectional"))
    )
    (net (code "40") (name "B33") (class "Default")
      (node (ref "IC5") (pin "7") (pinfunction "A5_7") (pintype "bidirectional"))
      (node (ref "U$1") (pin "P$33") (pinfunction "~{D1XX}_P$33") (pintype "bidirectional"))
    )
    (net (code "41") (name "B34") (class "Default")
      (node (ref "IC5") (pin "6") (pinfunction "A4_6") (pintype "bidirectional"))
      (node (ref "U$1") (pin "P$41") (pinfunction "A13_P$41") (pintype "bidirectional"))
    )
    (net (code "42") (name "B35") (class "Default")
      (node (ref "IC5") (pin "5") (pinfunction "A3_5") (pintype "bidirectional"))
      (node (ref "U$1") (pin "P$34") (pinfunction "~{MPD}_P$34") (pintype "bidirectional"))
    )
    (net (code "43") (name "B36") (class "Default")
      (node (ref "IC5") (pin "4") (pinfunction "A2_4") (pintype "bidirectional"))
      (node (ref "U$1") (pin "P$42") (pinfunction "A14_P$42") (pintype "bidirectional"))
    )
    (net (code "44") (name "B37") (class "Default")
      (node (ref "IC5") (pin "3") (pinfunction "A1_3") (pintype "bidirectional"))
      (node (ref "U$1") (pin "P$43") (pinfunction "A15_P$43") (pintype "bidirectional"))
    )
    (net (code "45") (name "B38") (class "Default")
      (node (ref "IC5") (pin "2") (pinfunction "A0_2") (pintype "bidirectional"))
      (node (ref "U$1") (pin "P$36") (pinfunction "~{REF}_P$36") (pintype "bidirectional"))
    )
    (net (code "46") (name "DOUT1_N") (class "Default")
      (node (ref "U$12") (pin "8") (pinfunction "DOUT1-_8") (pintype "bidirectional"))
      (node (ref "X1") (pin "3") (pinfunction "3_3") (pintype "passive"))
    )
    (net (code "47") (name "DOUT1_P") (class "Default")
      (node (ref "U$12") (pin "7") (pinfunction "DOUT1+_7") (pintype "bidirectional"))
      (node (ref "X1") (pin "6") (pinfunction "6_6") (pintype "passive"))
    )
    (net (code "48") (name "DOUT2_N") (class "Default")
      (node (ref "U$12") (pin "5") (pinfunction "DOUT2-_5") (pintype "bidirectional"))
      (node (ref "X1") (pin "7") (pinfunction "7_7") (pintype "passive"))
    )
    (net (code "49") (name "DOUT2_P") (class "Default")
      (node (ref "U$12") (pin "6") (pinfunction "DOUT2+_6") (pintype "bidirectional"))
      (node (ref "X1") (pin "8") (pinfunction "8_8") (pintype "passive"))
    )
    (net (code "50") (name "EN_1V0") (class "Default")
      (node (ref "R27") (pin "1") (pinfunction "1_1") (pintype "passive"))
      (node (ref "U$5") (pin "5") (pinfunction "EN_5") (pintype "bidirectional"))
      (node (ref "U$6") (pin "1") (pinfunction "~{RESET}_1") (pintype "bidirectional"))
    )
    (net (code "51") (name "GND") (class "Default")
      (node (ref "BOOT_SW") (pin "3") (pinfunction "3_3") (pintype "passive"))
      (node (ref "BOOT_SW") (pin "4") (pinfunction "4_4") (pintype "passive"))
      (node (ref "C1") (pin "2") (pinfunction "2_2") (pintype "passive"))
      (node (ref "C10") (pin "2") (pinfunction "2_2") (pintype "passive"))
      (node (ref "C11") (pin "2") (pinfunction "2_2") (pintype "passive"))
      (node (ref "C12") (pin "2") (pinfunction "2_2") (pintype "passive"))
      (node (ref "C13") (pin "2") (pinfunction "2_2") (pintype "passive"))
      (node (ref "C14") (pin "2") (pinfunction "2_2") (pintype "passive"))
      (node (ref "C15") (pin "2") (pinfunction "2_2") (pintype "passive"))
      (node (ref "C16") (pin "2") (pinfunction "2_2") (pintype "passive"))
      (node (ref "C17") (pin "2") (pinfunction "2_2") (pintype "passive"))
      (node (ref "C18") (pin "2") (pinfunction "2_2") (pintype "passive"))
      (node (ref "C19") (pin "2") (pinfunction "2_2") (pintype "passive"))
      (node (ref "C2") (pin "2") (pinfunction "2_2") (pintype "passive"))
      (node (ref "C20") (pin "2") (pinfunction "2_2") (pintype "passive"))
      (node (ref "C21") (pin "2") (pinfunction "2_2") (pintype "passive"))
      (node (ref "C23") (pin "2") (pinfunction "2_2") (pintype "passive"))
      (node (ref "C24") (pin "2") (pinfunction "2_2") (pintype "passive"))
      (node (ref "C25") (pin "1") (pinfunction "1_1") (pintype "passive"))
      (node (ref "C26") (pin "2") (pinfunction "2_2") (pintype "passive"))
      (node (ref "C27") (pin "-") (pinfunction "-_-") (pintype "passive"))
      (node (ref "C29") (pin "-") (pinfunction "-_-") (pintype "passive"))
      (node (ref "C3") (pin "2") (pinfunction "2_2") (pintype "passive"))
      (node (ref "C30") (pin "-") (pinfunction "-_-") (pintype "passive"))
      (node (ref "C32") (pin "-") (pinfunction "-_-") (pintype "passive"))
      (node (ref "C34") (pin "2") (pinfunction "2_2") (pintype "passive"))
      (node (ref "C35") (pin "2") (pinfunction "2_2") (pintype "passive"))
      (node (ref "C36") (pin "2") (pinfunction "2_2") (pintype "passive"))
      (node (ref "C37") (pin "2") (pinfunction "2_2") (pintype "passive"))
      (node (ref "C38") (pin "2") (pinfunction "2_2") (pintype "passive"))
      (node (ref "C39") (pin "2") (pinfunction "2_2") (pintype "passive"))
      (node (ref "C4") (pin "2") (pinfunction "2_2") (pintype "passive"))
      (node (ref "C40") (pin "2") (pinfunction "2_2") (pintype "passive"))
      (node (ref "C41") (pin "2") (pinfunction "2_2") (pintype "passive"))
      (node (ref "C42") (pin "2") (pinfunction "2_2") (pintype "passive"))
      (node (ref "C43") (pin "2") (pinfunction "2_2") (pintype "passive"))
      (node (ref "C44") (pin "1") (pinfunction "1_1") (pintype "passive"))
      (node (ref "C45") (pin "2") (pinfunction "2_2") (pintype "passive"))
      (node (ref "C46") (pin "2") (pinfunction "2_2") (pintype "passive"))
      (node (ref "C5") (pin "2") (pinfunction "2_2") (pintype "passive"))
      (node (ref "C6") (pin "2") (pinfunction "2_2") (pintype "passive"))
      (node (ref "C7") (pin "2") (pinfunction "2_2") (pintype "passive"))
      (node (ref "C8") (pin "2") (pinfunction "2_2") (pintype "passive"))
      (node (ref "C9") (pin "2") (pinfunction "2_2") (pintype "passive"))
      (node (ref "IC1") (pin "10") (pinfunction "GND_10") (pintype "power_in"))
      (node (ref "IC1") (pin "19") (pinfunction "_OE_19") (pintype "bidirectional"))
      (node (ref "IC2") (pin "10") (pinfunction "GND_10") (pintype "power_in"))
      (node (ref "IC2") (pin "19") (pinfunction "_OE_19") (pintype "bidirectional"))
      (node (ref "IC3") (pin "10") (pinfunction "GND_10") (pintype "power_in"))
      (node (ref "IC3") (pin "19") (pinfunction "_OE_19") (pintype "bidirectional"))
      (node (ref "IC4") (pin "10") (pinfunction "GND_10") (pintype "power_in"))
      (node (ref "IC4") (pin "19") (pinfunction "_OE_19") (pintype "bidirectional"))
      (node (ref "IC5") (pin "10") (pinfunction "GND_10") (pintype "power_in"))
      (node (ref "IC5") (pin "19") (pinfunction "_OE_19") (pintype "bidirectional"))
      (node (ref "R18") (pin "1") (pinfunction "1_1") (pintype "passive"))
      (node (ref "R19") (pin "1") (pinfunction "1_1") (pintype "passive"))
      (node (ref "R20") (pin "2") (pinfunction "2_2") (pintype "passive"))
      (node (ref "R21") (pin "2") (pinfunction "2_2") (pintype "passive"))
      (node (ref "R22") (pin "2") (pinfunction "2_2") (pintype "passive"))
      (node (ref "R23") (pin "2") (pinfunction "2_2") (pintype "passive"))
      (node (ref "R26") (pin "2") (pinfunction "2_2") (pintype "passive"))
      (node (ref "R4") (pin "1") (pinfunction "1_1") (pintype "passive"))
      (node (ref "R5") (pin "1") (pinfunction "1_1") (pintype "passive"))
      (node (ref "R7") (pin "1") (pinfunction "1_1") (pintype "passive"))
      (node (ref "R9") (pin "1") (pinfunction "1_1") (pintype "passive"))
      (node (ref "RESET_SW") (pin "3") (pinfunction "3_3") (pintype "passive"))
      (node (ref "RESET_SW") (pin "4") (pinfunction "4_4") (pintype "passive"))
      (node (ref "SJ1") (pin "1") (pinfunction "1_1") (pintype "passive"))
      (node (ref "U$1") (pin "P$2") (pinfunction "GND_P$2") (pintype "bidirectional"))
      (node (ref "U$1") (pin "P$44") (pinfunction "GND_P$44") (pintype "bidirectional"))
      (node (ref "U$10") (pin "4") (pinfunction "GND_4") (pintype "bidirectional"))
      (node (ref "U$11") (pin "2") (pinfunction "GND_2") (pintype "bidirectional"))
      (node (ref "U$12") (pin "13") (pinfunction "GND_13") (pintype "bidirectional"))
      (node (ref "U$12") (pin "9") (pinfunction "~{EN}_9") (pintype "bidirectional"))
      (node (ref "U$2") (pin "PAD") (pinfunction "GND_PAD") (pintype "bidirectional"))
      (node (ref "U$3") (pin "3") (pinfunction "GND_3") (pintype "bidirectional"))
      (node (ref "U$4") (pin "1") (pinfunction "GND_1") (pintype "bidirectional"))
      (node (ref "U$5") (pin "1") (pinfunction "GND_1") (pintype "bidirectional"))
      (node (ref "U$6") (pin "2") (pinfunction "GND_2") (pintype "bidirectional"))
      (node (ref "U$7") (pin "12") (pinfunction "VSSQ_12") (pintype "bidirectional"))
      (node (ref "U$7") (pin "28") (pinfunction "VSS_28") (pintype "bidirectional"))
      (node (ref "U$7") (pin "41") (pinfunction "VSS_41") (pintype "bidirectional"))
      (node (ref "U$7") (pin "46") (pinfunction "VSSQ_46") (pintype "bidirectional"))
      (node (ref "U$7") (pin "52") (pinfunction "VSSQ_52") (pintype "bidirectional"))
      (node (ref "U$7") (pin "54") (pinfunction "VSS_54") (pintype "bidirectional"))
      (node (ref "U$7") (pin "6") (pinfunction "VSSQ_6") (pintype "bidirectional"))
      (node (ref "U$8") (pin "3") (pinfunction "GND_3") (pintype "power_in"))
      (node (ref "U$9") (pin "15") (pinfunction "OE_15") (pintype "bidirectional"))
      (node (ref "U$9") (pin "8") (pinfunction "GND_8") (pintype "bidirectional"))
      (node (ref "U1") (pin "2") (pinfunction "GND_2") (pintype "bidirectional"))
      (node (ref "U2") (pin "6") (pinfunction "GND_6") (pintype "bidirectional"))
      (node (ref "U2") (pin "CD1") (pinfunction "SHIELD_CD1") (pintype "bidirectional"))
      (node (ref "U2") (pin "CD2") (pinfunction "SHIELD_CD2") (pintype "bidirectional"))
      (node (ref "U2") (pin "GND1") (pinfunction "SHIELD_GND1") (pintype "bidirectional"))
      (node (ref "U2") (pin "GND3") (pinfunction "SHIELD_GND3") (pintype "bidirectional"))
      (node (ref "USBPOWER") (pin "5") (pinfunction "5_5") (pintype "input"))
      (node (ref "X1") (pin "S@1") (pinfunction "S1_S@1") (pintype "passive"))
      (node (ref "X1") (pin "S@2") (pinfunction "S2_S@2") (pintype "passive"))
      (node (ref "XTAG") (pin "12") (pinfunction "12_12") (pintype "passive"))
      (node (ref "XTAG") (pin "16") (pinfunction "16_16") (pintype "passive"))
      (node (ref "XTAG") (pin "20") (pinfunction "20_20") (pintype "passive"))
      (node (ref "XTAG") (pin "4") (pinfunction "4_4") (pintype "passive"))
      (node (ref "XTAG") (pin "8") (pinfunction "8_8") (pintype "passive"))
    )
    (net (code "52") (name "JTAG_DN0") (class "Default")
      (node (ref "U$2") (pin "8") (pinfunction "X0D41_8") (pintype "bidirectional"))
      (node (ref "XTAG") (pin "14") (pinfunction "14_14") (pintype "passive"))
    )
    (net (code "53") (name "JTAG_DN1") (class "Default")
      (node (ref "U$2") (pin "7") (pinfunction "X0D40_7") (pintype "bidirectional"))
      (node (ref "XTAG") (pin "18") (pinfunction "18_18") (pintype "passive"))
    )
    (net (code "54") (name "JTAG_UP0") (class "Default")
      (node (ref "R12") (pin "2") (pinfunction "2_2") (pintype "passive"))
      (node (ref "XTAG") (pin "10") (pinfunction "10_10") (pintype "passive"))
    )
    (net (code "55") (name "JTAG_UP1") (class "Default")
      (node (ref "R13") (pin "2") (pinfunction "2_2") (pintype "passive"))
      (node (ref "XTAG") (pin "6") (pinfunction "6_6") (pintype "passive"))
    )
    (net (code "56") (name "LED0") (class "Default")
      (node (ref "DBG0") (pin "A") (pinfunction "A_A") (pintype "passive"))
      (node (ref "U$2") (pin "95") (pinfunction "X0D28_95") (pintype "bidirectional"))
    )
    (net (code "57") (name "LED1") (class "Default")
      (node (ref "DBG1") (pin "A") (pinfunction "A_A") (pintype "passive"))
      (node (ref "U$2") (pin "97") (pinfunction "X0D29_97") (pintype "bidirectional"))
    )
    (net (code "58") (name "LED2") (class "Default")
      (node (ref "DBG2") (pin "A") (pinfunction "A_A") (pintype "passive"))
      (node (ref "U$2") (pin "98") (pinfunction "X0D30_98") (pintype "bidirectional"))
    )
    (net (code "59") (name "LED3") (class "Default")
      (node (ref "DBG3") (pin "A") (pinfunction "A_A") (pintype "passive"))
      (node (ref "U$2") (pin "99") (pinfunction "X0D31_99") (pintype "bidirectional"))
    )
    (net (code "60") (name "LNK_IN0") (class "Default")
      (node (ref "R18") (pin "2") (pinfunction "2_2") (pintype "passive"))
      (node (ref "U$12") (pin "14") (pinfunction "ROUT2_14") (pintype "bidirectional"))
      (node (ref "U$2") (pin "87") (pinfunction "X0D24_87") (pintype "bidirectional"))
    )
    (net (code "61") (name "LNK_IN1") (class "Default")
      (node (ref "R19") (pin "2") (pinfunction "2_2") (pintype "passive"))
      (node (ref "U$12") (pin "15") (pinfunction "ROUT1_15") (pintype "bidirectional"))
      (node (ref "U$2") (pin "85") (pinfunction "X1D01_85") (pintype "bidirectional"))
    )
    (net (code "62") (name "LNK_OUT0") (class "Default")
      (node (ref "R17") (pin "2") (pinfunction "2_2") (pintype "passive"))
      (node (ref "U$12") (pin "11") (pinfunction "DIN2_11") (pintype "bidirectional"))
    )
    (net (code "63") (name "LNK_OUT1") (class "Default")
      (node (ref "R16") (pin "2") (pinfunction "2_2") (pintype "passive"))
      (node (ref "U$12") (pin "10") (pinfunction "DIN1_10") (pintype "bidirectional"))
    )
    (net (code "64") (name "Net-(DBG0-PadC)") (class "Default")
      (node (ref "DBG0") (pin "C") (pinfunction "C_C") (pintype "passive"))
      (node (ref "R20") (pin "1") (pinfunction "1_1") (pintype "passive"))
    )
    (net (code "65") (name "Net-(DBG1-PadC)") (class "Default")
      (node (ref "DBG1") (pin "C") (pinfunction "C_C") (pintype "passive"))
      (node (ref "R21") (pin "1") (pinfunction "1_1") (pintype "passive"))
    )
    (net (code "66") (name "Net-(DBG2-PadC)") (class "Default")
      (node (ref "DBG2") (pin "C") (pinfunction "C_C") (pintype "passive"))
      (node (ref "R22") (pin "1") (pinfunction "1_1") (pintype "passive"))
    )
    (net (code "67") (name "Net-(DBG3-PadC)") (class "Default")
      (node (ref "DBG3") (pin "C") (pinfunction "C_C") (pintype "passive"))
      (node (ref "R23") (pin "1") (pinfunction "1_1") (pintype "passive"))
    )
    (net (code "68") (name "Net-(LED1-PadC)") (class "Default")
      (node (ref "LED1") (pin "C") (pinfunction "C_C") (pintype "passive"))
      (node (ref "R5") (pin "2") (pinfunction "2_2") (pintype "passive"))
    )
    (net (code "69") (name "Net-(U$2A-CLK)") (class "Default")
      (node (ref "U$2") (pin "124") (pinfunction "CLK_124") (pintype "bidirectional"))
      (node (ref "U1") (pin "3") (pinfunction "OUT_3") (pintype "bidirectional"))
    )
    (net (code "70") (name "Net-(U$2B-PLL_AGND)") (class "Default")
      (node (ref "C22") (pin "2") (pinfunction "2_2") (pintype "passive"))
      (node (ref "SJ1") (pin "2") (pinfunction "2_2") (pintype "passive"))
      (node (ref "U$2") (pin "103") (pinfunction "PLL_AGND_103") (pintype "bidirectional"))
    )
    (net (code "71") (name "Net-(U$2B-PLL_AVDD_1)") (class "Default")
      (node (ref "C22") (pin "1") (pinfunction "1_1") (pintype "passive"))
      (node (ref "R1") (pin "1") (pinfunction "1_1") (pintype "passive"))
      (node (ref "U$2") (pin "102") (pinfunction "PLL_AVDD_1_102") (pintype "bidirectional"))
    )
    (net (code "72") (name "Net-(U$2C-X0D25)") (class "Default")
      (node (ref "R17") (pin "1") (pinfunction "1_1") (pintype "passive"))
      (node (ref "U$2") (pin "88") (pinfunction "X0D25_88") (pintype "bidirectional"))
    )
    (net (code "73") (name "Net-(U$2C-X0D34)") (class "Default")
      (node (ref "R16") (pin "1") (pinfunction "1_1") (pintype "passive"))
      (node (ref "U$2") (pin "89") (pinfunction "X0D34_89") (pintype "bidirectional"))
    )
    (net (code "74") (name "Net-(U$2C-X0D39)") (class "Default")
      (node (ref "BOOT_SW") (pin "1") (pinfunction "1_1") (pintype "passive"))
      (node (ref "BOOT_SW") (pin "2") (pinfunction "2_2") (pintype "passive"))
      (node (ref "R15") (pin "1") (pinfunction "1_1") (pintype "passive"))
      (node (ref "U$2") (pin "6") (pinfunction "X0D39_6") (pintype "bidirectional"))
    )
    (net (code "75") (name "Net-(U$2C-X0D42)") (class "Default")
      (node (ref "R12") (pin "1") (pinfunction "1_1") (pintype "passive"))
      (node (ref "U$2") (pin "10") (pinfunction "X0D42_10") (pintype "bidirectional"))
    )
    (net (code "76") (name "Net-(U$2C-X0D43)") (class "Default")
      (node (ref "R13") (pin "1") (pinfunction "1_1") (pintype "passive"))
      (node (ref "U$2") (pin "11") (pinfunction "X0D43_11") (pintype "bidirectional"))
    )
    (net (code "77") (name "Net-(U$3-A)") (class "Default")
      (node (ref "R2") (pin "1") (pinfunction "1_1") (pintype "passive"))
      (node (ref "U$3") (pin "2") (pinfunction "A_2") (pintype "bidirectional"))
      (node (ref "XTAG") (pin "15") (pinfunction "15_15") (pintype "passive"))
    )
    (net (code "78") (name "Net-(U$4-SW)") (class "Default")
      (node (ref "C28") (pin "1") (pinfunction "1_1") (pintype "passive"))
      (node (ref "L1") (pin "2") (pinfunction "2_2") (pintype "passive"))
      (node (ref "U$4") (pin "2") (pinfunction "SW_2") (pintype "bidirectional"))
    )
    (net (code "79") (name "Net-(U$4-VBST)") (class "Default")
      (node (ref "C28") (pin "2") (pinfunction "2_2") (pintype "passive"))
      (node (ref "U$4") (pin "6") (pinfunction "VBST_6") (pintype "bidirectional"))
    )
    (net (code "80") (name "Net-(U$4-VFB)") (class "Default")
      (node (ref "R3") (pin "1") (pinfunction "1_1") (pintype "passive"))
      (node (ref "R4") (pin "2") (pinfunction "2_2") (pintype "passive"))
      (node (ref "U$4") (pin "4") (pinfunction "VFB_4") (pintype "bidirectional"))
    )
    (net (code "81") (name "Net-(U$5-SW)") (class "Default")
      (node (ref "C31") (pin "1") (pinfunction "1_1") (pintype "passive"))
      (node (ref "L2") (pin "2") (pinfunction "2_2") (pintype "passive"))
      (node (ref "U$5") (pin "2") (pinfunction "SW_2") (pintype "bidirectional"))
    )
    (net (code "82") (name "Net-(U$5-VBST)") (class "Default")
      (node (ref "C31") (pin "2") (pinfunction "2_2") (pintype "passive"))
      (node (ref "U$5") (pin "6") (pinfunction "VBST_6") (pintype "bidirectional"))
    )
    (net (code "83") (name "Net-(U$5-VFB)") (class "Default")
      (node (ref "R6") (pin "1") (pinfunction "1_1") (pintype "passive"))
      (node (ref "R7") (pin "2") (pinfunction "2_2") (pintype "passive"))
      (node (ref "U$5") (pin "4") (pinfunction "VFB_4") (pintype "bidirectional"))
    )
    (net (code "84") (name "Net-(U$6-CT)") (class "Default")
      (node (ref "C34") (pin "1") (pinfunction "1_1") (pintype "passive"))
      (node (ref "U$6") (pin "4") (pinfunction "CT_4") (pintype "bidirectional"))
    )
    (net (code "85") (name "Net-(U$7-CKE)") (class "Default")
      (node (ref "R8") (pin "2") (pinfunction "2_2") (pintype "passive"))
      (node (ref "U$7") (pin "37") (pinfunction "CKE_37") (pintype "bidirectional"))
    )
    (net (code "86") (name "Net-(U$7-LDQM)") (class "Default")
      (node (ref "U$7") (pin "15") (pinfunction "LDQM_15") (pintype "bidirectional"))
      (node (ref "U$7") (pin "39") (pinfunction "UDQM_39") (pintype "bidirectional"))
      (node (ref "U$8") (pin "4") (pinfunction "O_4") (pintype "output"))
    )
    (net (code "87") (name "Net-(U$7-~{CS})") (class "Default")
      (node (ref "R9") (pin "2") (pinfunction "2_2") (pintype "passive"))
      (node (ref "U$7") (pin "19") (pinfunction "~{CS}_19") (pintype "bidirectional"))
    )
    (net (code "88") (name "Net-(U$10-SI{slash}IO0)") (class "Default")
      (node (ref "U$10") (pin "5") (pinfunction "SI/IO0_5") (pintype "bidirectional"))
      (node (ref "U$9") (pin "3") (pinfunction "1B2_3") (pintype "bidirectional"))
    )
    (net (code "89") (name "Net-(U$10-SO{slash}IO1)") (class "Default")
      (node (ref "U$10") (pin "2") (pinfunction "SO/IO1_2") (pintype "bidirectional"))
      (node (ref "U$9") (pin "6") (pinfunction "2B2_6") (pintype "bidirectional"))
    )
    (net (code "90") (name "Net-(U$10-~{HOLD}{slash}~{RESET}{slash}IO3)") (class "Default")
      (node (ref "U$10") (pin "7") (pinfunction "~{HOLD}/~{RESET}/IO3_7") (pintype "bidirectional"))
      (node (ref "U$9") (pin "13") (pinfunction "4B2_13") (pintype "bidirectional"))
    )
    (net (code "91") (name "Net-(U$10-~{WP}{slash}IO2)") (class "Default")
      (node (ref "U$10") (pin "3") (pinfunction "~{WP}/IO2_3") (pintype "bidirectional"))
      (node (ref "U$9") (pin "10") (pinfunction "3B2_10") (pintype "bidirectional"))
    )
    (net (code "92") (name "Net-(U$11-CT)") (class "Default")
      (node (ref "C43") (pin "1") (pinfunction "1_1") (pintype "passive"))
      (node (ref "U$11") (pin "4") (pinfunction "CT_4") (pintype "bidirectional"))
    )
    (net (code "93") (name "Net-(U$11-~{MR})") (class "Default")
      (node (ref "C44") (pin "2") (pinfunction "2_2") (pintype "passive"))
      (node (ref "RESET_SW") (pin "1") (pinfunction "1_1") (pintype "passive"))
      (node (ref "RESET_SW") (pin "2") (pinfunction "2_2") (pintype "passive"))
      (node (ref "U$11") (pin "3") (pinfunction "~{MR}_3") (pintype "bidirectional"))
    )
    (net (code "94") (name "QSPI_CLK") (class "Default")
      (node (ref "U$10") (pin "6") (pinfunction "SCK_6") (pintype "bidirectional"))
      (node (ref "U$2") (pin "28") (pinfunction "X0D10_28") (pintype "bidirectional"))
    )
    (net (code "95") (name "RIN1_N") (class "Default")
      (node (ref "U$12") (pin "1") (pinfunction "RIN1-_1") (pintype "bidirectional"))
      (node (ref "X1") (pin "1") (pinfunction "1_1") (pintype "passive"))
    )
    (net (code "96") (name "RIN1_P") (class "Default")
      (node (ref "U$12") (pin "2") (pinfunction "RIN1+_2") (pintype "bidirectional"))
      (node (ref "X1") (pin "2") (pinfunction "2_2") (pintype "passive"))
    )
    (net (code "97") (name "RIN2_N") (class "Default")
      (node (ref "U$12") (pin "4") (pinfunction "RIN2-_4") (pintype "bidirectional"))
      (node (ref "X1") (pin "4") (pinfunction "4_4") (pintype "passive"))
    )
    (net (code "98") (name "RIN2_P") (class "Default")
      (node (ref "U$12") (pin "3") (pinfunction "RIN2+_3") (pintype "bidirectional"))
      (node (ref "X1") (pin "5") (pinfunction "5_5") (pintype "passive"))
    )
    (net (code "99") (name "SDC_CLK") (class "Default")
      (node (ref "U$2") (pin "96") (pinfunction "X0D33_96") (pintype "bidirectional"))
      (node (ref "U2") (pin "5") (pinfunction "SCK_5") (pintype "bidirectional"))
    )
    (net (code "100") (name "SDC_CMD") (class "Default")
      (node (ref "R24") (pin "1") (pinfunction "1_1") (pintype "passive"))
      (node (ref "U$2") (pin "94") (pinfunction "X0D32_94") (pintype "bidirectional"))
      (node (ref "U2") (pin "3") (pinfunction "DI_3") (pintype "bidirectional"))
    )
    (net (code "101") (name "SDC_D0") (class "Default")
      (node (ref "R25") (pin "1") (pinfunction "1_1") (pintype "passive"))
      (node (ref "U$2") (pin "93") (pinfunction "X0D27_93") (pintype "bidirectional"))
      (node (ref "U2") (pin "7") (pinfunction "DO_7") (pintype "bidirectional"))
    )
    (net (code "102") (name "SDC_D1") (class "Default")
      (node (ref "U$2") (pin "92") (pinfunction "X0D26_92") (pintype "bidirectional"))
      (node (ref "U2") (pin "8") (pinfunction "RSV_8") (pintype "bidirectional"))
    )
    (net (code "103") (name "SDC_D2") (class "Default")
      (node (ref "U$2") (pin "64") (pinfunction "X0D23_64") (pintype "bidirectional"))
      (node (ref "U2") (pin "1") (pinfunction "NC_1") (pintype "bidirectional"))
    )
    (net (code "104") (name "SDC_D3") (class "Default")
      (node (ref "R26") (pin "1") (pinfunction "1_1") (pintype "passive"))
      (node (ref "U$2") (pin "63") (pinfunction "X0D22_63") (pintype "bidirectional"))
      (node (ref "U2") (pin "2") (pinfunction "CS_2") (pintype "bidirectional"))
    )
    (net (code "105") (name "SD_ADQ0") (class "Default")
      (node (ref "U$2") (pin "39") (pinfunction "X0D02_39") (pintype "bidirectional"))
      (node (ref "U$7") (pin "2") (pinfunction "DQ0_2") (pintype "bidirectional"))
      (node (ref "U$7") (pin "23") (pinfunction "A0_23") (pintype "bidirectional"))
    )
    (net (code "106") (name "SD_ADQ1") (class "Default")
      (node (ref "U$2") (pin "40") (pinfunction "X0D03_40") (pintype "bidirectional"))
      (node (ref "U$7") (pin "24") (pinfunction "A1_24") (pintype "bidirectional"))
      (node (ref "U$7") (pin "4") (pinfunction "DQ1_4") (pintype "bidirectional"))
    )
    (net (code "107") (name "SD_ADQ2") (class "Default")
      (node (ref "U$7") (pin "25") (pinfunction "A2_25") (pintype "bidirectional"))
      (node (ref "U$7") (pin "5") (pinfunction "DQ2_5") (pintype "bidirectional"))
      (node (ref "U$9") (pin "2") (pinfunction "1B1_2") (pintype "bidirectional"))
    )
    (net (code "108") (name "SD_ADQ2{slash}QS_D0") (class "Default")
      (node (ref "U$2") (pin "34") (pinfunction "X0D04_34") (pintype "bidirectional"))
      (node (ref "U$9") (pin "4") (pinfunction "1A_4") (pintype "bidirectional"))
    )
    (net (code "109") (name "SD_ADQ3") (class "Default")
      (node (ref "U$7") (pin "26") (pinfunction "A3_26") (pintype "bidirectional"))
      (node (ref "U$7") (pin "7") (pinfunction "DQ3_7") (pintype "bidirectional"))
      (node (ref "U$9") (pin "5") (pinfunction "2B1_5") (pintype "bidirectional"))
    )
    (net (code "110") (name "SD_ADQ3{slash}QS_D1") (class "Default")
      (node (ref "U$2") (pin "35") (pinfunction "X0D05_35") (pintype "bidirectional"))
      (node (ref "U$9") (pin "7") (pinfunction "2A_7") (pintype "bidirectional"))
    )
    (net (code "111") (name "SD_ADQ4") (class "Default")
      (node (ref "U$7") (pin "29") (pinfunction "A4_29") (pintype "bidirectional"))
      (node (ref "U$7") (pin "8") (pinfunction "DQ4_8") (pintype "bidirectional"))
      (node (ref "U$9") (pin "11") (pinfunction "3B1_11") (pintype "bidirectional"))
    )
    (net (code "112") (name "SD_ADQ4{slash}QS_D2") (class "Default")
      (node (ref "U$2") (pin "36") (pinfunction "X0D06_36") (pintype "bidirectional"))
      (node (ref "U$9") (pin "9") (pinfunction "3A_9") (pintype "bidirectional"))
    )
    (net (code "113") (name "SD_ADQ5") (class "Default")
      (node (ref "U$7") (pin "10") (pinfunction "DQ5_10") (pintype "bidirectional"))
      (node (ref "U$7") (pin "30") (pinfunction "A5_30") (pintype "bidirectional"))
      (node (ref "U$9") (pin "14") (pinfunction "4B1_14") (pintype "bidirectional"))
    )
    (net (code "114") (name "SD_ADQ5{slash}QS_D3") (class "Default")
      (node (ref "U$2") (pin "37") (pinfunction "X0D07_37") (pintype "bidirectional"))
      (node (ref "U$9") (pin "12") (pinfunction "4A_12") (pintype "bidirectional"))
    )
    (net (code "115") (name "SD_ADQ6") (class "Default")
      (node (ref "U$2") (pin "41") (pinfunction "X0D08_41") (pintype "bidirectional"))
      (node (ref "U$7") (pin "11") (pinfunction "DQ6_11") (pintype "bidirectional"))
      (node (ref "U$7") (pin "31") (pinfunction "A6_31") (pintype "bidirectional"))
    )
    (net (code "116") (name "SD_ADQ7") (class "Default")
      (node (ref "U$2") (pin "43") (pinfunction "X0D09_43") (pintype "bidirectional"))
      (node (ref "U$7") (pin "13") (pinfunction "DQ7_13") (pintype "bidirectional"))
      (node (ref "U$7") (pin "32") (pinfunction "A7_32") (pintype "bidirectional"))
    )
    (net (code "117") (name "SD_ADQ8") (class "Default")
      (node (ref "U$2") (pin "56") (pinfunction "X0D14_56") (pintype "bidirectional"))
      (node (ref "U$7") (pin "33") (pinfunction "A8_33") (pintype "bidirectional"))
      (node (ref "U$7") (pin "42") (pinfunction "DQ8_42") (pintype "bidirectional"))
    )
    (net (code "118") (name "SD_ADQ9") (class "Default")
      (node (ref "U$2") (pin "57") (pinfunction "X0D15_57") (pintype "bidirectional"))
      (node (ref "U$7") (pin "34") (pinfunction "A9_34") (pintype "bidirectional"))
      (node (ref "U$7") (pin "44") (pinfunction "DQ9_44") (pintype "bidirectional"))
    )
    (net (code "119") (name "SD_ADQ10") (class "Default")
      (node (ref "U$2") (pin "67") (pinfunction "X0D16_67") (pintype "bidirectional"))
      (node (ref "U$7") (pin "22") (pinfunction "A10/AP_22") (pintype "bidirectional"))
      (node (ref "U$7") (pin "45") (pinfunction "DQ10_45") (pintype "bidirectional"))
    )
    (net (code "120") (name "SD_ADQ11") (class "Default")
      (node (ref "U$2") (pin "68") (pinfunction "X0D17_68") (pintype "bidirectional"))
      (node (ref "U$7") (pin "35") (pinfunction "A11_35") (pintype "bidirectional"))
      (node (ref "U$7") (pin "47") (pinfunction "DQ11_47") (pintype "bidirectional"))
    )
    (net (code "121") (name "SD_ADQ12") (class "Default")
      (node (ref "U$2") (pin "69") (pinfunction "X0D18_69") (pintype "bidirectional"))
      (node (ref "U$7") (pin "36") (pinfunction "A12_36") (pintype "bidirectional"))
      (node (ref "U$7") (pin "48") (pinfunction "DQ12_48") (pintype "bidirectional"))
    )
    (net (code "122") (name "SD_ADQ13") (class "Default")
      (node (ref "U$2") (pin "70") (pinfunction "X0D19_70") (pintype "bidirectional"))
      (node (ref "U$7") (pin "20") (pinfunction "BS0_20") (pintype "bidirectional"))
      (node (ref "U$7") (pin "50") (pinfunction "DQ13_50") (pintype "bidirectional"))
    )
    (net (code "123") (name "SD_ADQ14") (class "Default")
      (node (ref "U$2") (pin "58") (pinfunction "X0D20_58") (pintype "bidirectional"))
      (node (ref "U$7") (pin "21") (pinfunction "BS1_21") (pintype "bidirectional"))
      (node (ref "U$7") (pin "51") (pinfunction "DQ14_51") (pintype "bidirectional"))
    )
    (net (code "124") (name "SD_ADQ15") (class "Default")
      (node (ref "U$2") (pin "60") (pinfunction "X0D21_60") (pintype "bidirectional"))
      (node (ref "U$7") (pin "53") (pinfunction "DQ15_53") (pintype "bidirectional"))
    )
    (net (code "125") (name "SD_CLK") (class "Default")
      (node (ref "U$2") (pin "5") (pinfunction "X0D38_5") (pintype "bidirectional"))
      (node (ref "U$7") (pin "38") (pinfunction "CLK_38") (pintype "bidirectional"))
    )
    (net (code "126") (name "TCK") (class "Default")
      (node (ref "U$2") (pin "127") (pinfunction "TCK_127") (pintype "bidirectional"))
      (node (ref "XTAG") (pin "9") (pinfunction "9_9") (pintype "passive"))
    )
    (net (code "127") (name "TDI") (class "Default")
      (node (ref "U$2") (pin "128") (pinfunction "TDI_128") (pintype "bidirectional"))
      (node (ref "XTAG") (pin "5") (pinfunction "5_5") (pintype "passive"))
    )
    (net (code "128") (name "TDO") (class "Default")
      (node (ref "U$2") (pin "1") (pinfunction "TDO_1") (pintype "bidirectional"))
      (node (ref "XTAG") (pin "13") (pinfunction "13_13") (pintype "passive"))
    )
    (net (code "129") (name "TMS") (class "Default")
      (node (ref "U$2") (pin "126") (pinfunction "TMS_126") (pintype "bidirectional"))
      (node (ref "XTAG") (pin "7") (pinfunction "7_7") (pintype "passive"))
    )
    (net (code "130") (name "VCCINT") (class "Default")
      (node (ref "C10") (pin "1") (pinfunction "1_1") (pintype "passive"))
      (node (ref "C11") (pin "1") (pinfunction "1_1") (pintype "passive"))
      (node (ref "C12") (pin "1") (pinfunction "1_1") (pintype "passive"))
      (node (ref "C13") (pin "1") (pinfunction "1_1") (pintype "passive"))
      (node (ref "C23") (pin "1") (pinfunction "1_1") (pintype "passive"))
      (node (ref "C32") (pin "+") (pinfunction "+_+") (pintype "passive"))
      (node (ref "C6") (pin "1") (pinfunction "1_1") (pintype "passive"))
      (node (ref "C7") (pin "1") (pinfunction "1_1") (pintype "passive"))
      (node (ref "C8") (pin "1") (pinfunction "1_1") (pintype "passive"))
      (node (ref "C9") (pin "1") (pinfunction "1_1") (pintype "passive"))
      (node (ref "L2") (pin "1") (pinfunction "1_1") (pintype "passive"))
      (node (ref "R1") (pin "2") (pinfunction "2_2") (pintype "passive"))
      (node (ref "R6") (pin "2") (pinfunction "2_2") (pintype "passive"))
      (node (ref "U$11") (pin "5") (pinfunction "SENSE_5") (pintype "bidirectional"))
      (node (ref "U$2") (pin "100") (pinfunction "VDD_1_100") (pintype "bidirectional"))
      (node (ref "U$2") (pin "101") (pinfunction "VDD_1_101") (pintype "bidirectional"))
      (node (ref "U$2") (pin "119") (pinfunction "VDD_1_119") (pintype "bidirectional"))
      (node (ref "U$2") (pin "125") (pinfunction "VDD_1_125") (pintype "bidirectional"))
      (node (ref "U$2") (pin "16") (pinfunction "VDD_1_16") (pintype "bidirectional"))
      (node (ref "U$2") (pin "17") (pinfunction "VDD_1_17") (pintype "bidirectional"))
      (node (ref "U$2") (pin "24") (pinfunction "VDD_1_24") (pintype "bidirectional"))
      (node (ref "U$2") (pin "38") (pinfunction "VDD_1_38") (pintype "bidirectional"))
      (node (ref "U$2") (pin "42") (pinfunction "VDD_1_42") (pintype "bidirectional"))
      (node (ref "U$2") (pin "47") (pinfunction "VDD_1_47") (pintype "bidirectional"))
      (node (ref "U$2") (pin "55") (pinfunction "VDD_1_55") (pintype "bidirectional"))
      (node (ref "U$2") (pin "59") (pinfunction "VDD_1_59") (pintype "bidirectional"))
      (node (ref "U$2") (pin "72") (pinfunction "VDD_1_72") (pintype "bidirectional"))
      (node (ref "U$2") (pin "79") (pinfunction "VDD_1_79") (pintype "bidirectional"))
      (node (ref "U$2") (pin "80") (pinfunction "VDD_1_80") (pintype "bidirectional"))
      (node (ref "U$2") (pin "86") (pinfunction "VDD_1_86") (pintype "bidirectional"))
      (node (ref "U$2") (pin "9") (pinfunction "VDD_1_9") (pintype "bidirectional"))
      (node (ref "U$6") (pin "5") (pinfunction "SENSE_5") (pintype "bidirectional"))
    )
    (net (code "131") (name "VCCIO") (class "Default")
      (node (ref "C14") (pin "1") (pinfunction "1_1") (pintype "passive"))
      (node (ref "C15") (pin "1") (pinfunction "1_1") (pintype "passive"))
      (node (ref "C16") (pin "1") (pinfunction "1_1") (pintype "passive"))
      (node (ref "C17") (pin "1") (pinfunction "1_1") (pintype "passive"))
      (node (ref "C18") (pin "1") (pinfunction "1_1") (pintype "passive"))
      (node (ref "C19") (pin "1") (pinfunction "1_1") (pintype "passive"))
      (node (ref "C20") (pin "1") (pinfunction "1_1") (pintype "passive"))
      (node (ref "C21") (pin "1") (pinfunction "1_1") (pintype "passive"))
      (node (ref "C24") (pin "1") (pinfunction "1_1") (pintype "passive"))
      (node (ref "C25") (pin "2") (pinfunction "2_2") (pintype "passive"))
      (node (ref "C26") (pin "1") (pinfunction "1_1") (pintype "passive"))
      (node (ref "C29") (pin "+") (pinfunction "+_+") (pintype "passive"))
      (node (ref "C35") (pin "1") (pinfunction "1_1") (pintype "passive"))
      (node (ref "C36") (pin "1") (pinfunction "1_1") (pintype "passive"))
      (node (ref "C37") (pin "1") (pinfunction "1_1") (pintype "passive"))
      (node (ref "C38") (pin "1") (pinfunction "1_1") (pintype "passive"))
      (node (ref "C39") (pin "1") (pinfunction "1_1") (pintype "passive"))
      (node (ref "C40") (pin "1") (pinfunction "1_1") (pintype "passive"))
      (node (ref "C41") (pin "1") (pinfunction "1_1") (pintype "passive"))
      (node (ref "C42") (pin "1") (pinfunction "1_1") (pintype "passive"))
      (node (ref "C45") (pin "1") (pinfunction "1_1") (pintype "passive"))
      (node (ref "C46") (pin "1") (pinfunction "1_1") (pintype "passive"))
      (node (ref "L1") (pin "1") (pinfunction "1_1") (pintype "passive"))
      (node (ref "LED1") (pin "A") (pinfunction "A_A") (pintype "passive"))
      (node (ref "R10") (pin "1") (pinfunction "1_1") (pintype "passive"))
      (node (ref "R11") (pin "1") (pinfunction "1_1") (pintype "passive"))
      (node (ref "R14") (pin "2") (pinfunction "2_2") (pintype "passive"))
      (node (ref "R15") (pin "2") (pinfunction "2_2") (pintype "passive"))
      (node (ref "R2") (pin "2") (pinfunction "2_2") (pintype "passive"))
      (node (ref "R24") (pin "2") (pinfunction "2_2") (pintype "passive"))
      (node (ref "R25") (pin "2") (pinfunction "2_2") (pintype "passive"))
      (node (ref "R27") (pin "2") (pinfunction "2_2") (pintype "passive"))
      (node (ref "R3") (pin "2") (pinfunction "2_2") (pintype "passive"))
      (node (ref "R8") (pin "1") (pinfunction "1_1") (pintype "passive"))
      (node (ref "U$10") (pin "8") (pinfunction "VCC_8") (pintype "bidirectional"))
      (node (ref "U$11") (pin "6") (pinfunction "VDD_6") (pintype "bidirectional"))
      (node (ref "U$12") (pin "12") (pinfunction "VCC_12") (pintype "bidirectional"))
      (node (ref "U$12") (pin "16") (pinfunction "EN_16") (pintype "bidirectional"))
      (node (ref "U$2") (pin "104") (pinfunction "OTP_VCC_33_104") (pintype "bidirectional"))
      (node (ref "U$2") (pin "109") (pinfunction "VDDIOT_33_109") (pintype "bidirectional"))
      (node (ref "U$2") (pin "110") (pinfunction "VDDIOT_33_110") (pintype "bidirectional"))
      (node (ref "U$2") (pin "13") (pinfunction "VDDIOL_33_13") (pintype "bidirectional"))
      (node (ref "U$2") (pin "19") (pinfunction "VDDIOL_33_19") (pintype "bidirectional"))
      (node (ref "U$2") (pin "29") (pinfunction "VDDIOL_33_29") (pintype "bidirectional"))
      (node (ref "U$2") (pin "4") (pinfunction "VDDIOL_33_4") (pintype "bidirectional"))
      (node (ref "U$2") (pin "46") (pinfunction "VDDIOL_33_46") (pintype "bidirectional"))
      (node (ref "U$2") (pin "48") (pinfunction "VDDIOR_33_48") (pintype "bidirectional"))
      (node (ref "U$2") (pin "66") (pinfunction "VDDIOR_33_66") (pintype "bidirectional"))
      (node (ref "U$2") (pin "77") (pinfunction "VDDIOR_33_77") (pintype "bidirectional"))
      (node (ref "U$2") (pin "82") (pinfunction "VDDIOR_33_82") (pintype "bidirectional"))
      (node (ref "U$2") (pin "91") (pinfunction "VDDIOR_33_91") (pintype "bidirectional"))
      (node (ref "U$3") (pin "5") (pinfunction "VCC_5") (pintype "bidirectional"))
      (node (ref "U$6") (pin "6") (pinfunction "VCC_6") (pintype "bidirectional"))
      (node (ref "U$7") (pin "1") (pinfunction "VDD_1") (pintype "bidirectional"))
      (node (ref "U$7") (pin "14") (pinfunction "VDD_14") (pintype "bidirectional"))
      (node (ref "U$7") (pin "27") (pinfunction "VDD_27") (pintype "bidirectional"))
      (node (ref "U$7") (pin "3") (pinfunction "VDDQ_3") (pintype "bidirectional"))
      (node (ref "U$7") (pin "43") (pinfunction "VDDQ_43") (pintype "bidirectional"))
      (node (ref "U$7") (pin "49") (pinfunction "VDDQ_49") (pintype "bidirectional"))
      (node (ref "U$7") (pin "9") (pinfunction "VDDQ_9") (pintype "bidirectional"))
      (node (ref "U$8") (pin "5") (pinfunction "VCC_5") (pintype "power_in"))
      (node (ref "U$9") (pin "16") (pinfunction "VCC_16") (pintype "bidirectional"))
      (node (ref "U1") (pin "4") (pinfunction "VCC_4") (pintype "bidirectional"))
      (node (ref "U2") (pin "4") (pinfunction "VCC_4") (pintype "bidirectional"))
    )
    (net (code "132") (name "X_A0") (class "Default")
      (node (ref "IC2") (pin "11") (pinfunction "B7_11") (pintype "bidirectional"))
      (node (ref "U$2") (pin "111") (pinfunction "X1D26_111") (pintype "bidirectional"))
    )
    (net (code "133") (name "X_A1") (class "Default")
      (node (ref "IC1") (pin "17") (pinfunction "B1_17") (pintype "bidirectional"))
      (node (ref "U$2") (pin "112") (pinfunction "X1D27_112") (pintype "bidirectional"))
    )
    (net (code "134") (name "X_A2") (class "Default")
      (node (ref "IC1") (pin "15") (pinfunction "B3_15") (pintype "bidirectional"))
      (node (ref "U$2") (pin "113") (pinfunction "X1D28_113") (pintype "bidirectional"))
    )
    (net (code "135") (name "X_A3") (class "Default")
      (node (ref "IC1") (pin "13") (pinfunction "B5_13") (pintype "bidirectional"))
      (node (ref "U$2") (pin "114") (pinfunction "X1D29_114") (pintype "bidirectional"))
    )
    (net (code "136") (name "X_A4") (class "Default")
      (node (ref "IC1") (pin "14") (pinfunction "B4_14") (pintype "bidirectional"))
      (node (ref "U$2") (pin "115") (pinfunction "X1D30_115") (pintype "bidirectional"))
    )
    (net (code "137") (name "X_A5") (class "Default")
      (node (ref "IC1") (pin "16") (pinfunction "B2_16") (pintype "bidirectional"))
      (node (ref "U$2") (pin "116") (pinfunction "X1D31_116") (pintype "bidirectional"))
    )
    (net (code "138") (name "X_A6") (class "Default")
      (node (ref "IC1") (pin "18") (pinfunction "B0_18") (pintype "bidirectional"))
      (node (ref "U$2") (pin "117") (pinfunction "X1D32_117") (pintype "bidirectional"))
    )
    (net (code "139") (name "X_A7") (class "Default")
      (node (ref "IC2") (pin "12") (pinfunction "B6_12") (pintype "bidirectional"))
      (node (ref "U$2") (pin "118") (pinfunction "X1D33_118") (pintype "bidirectional"))
    )
    (net (code "140") (name "X_A8") (class "Default")
      (node (ref "IC2") (pin "14") (pinfunction "B4_14") (pintype "bidirectional"))
      (node (ref "U$2") (pin "15") (pinfunction "X1D36_15") (pintype "bidirectional"))
    )
    (net (code "141") (name "X_A9") (class "Default")
      (node (ref "IC2") (pin "16") (pinfunction "B2_16") (pintype "bidirectional"))
      (node (ref "U$2") (pin "18") (pinfunction "X1D37_18") (pintype "bidirectional"))
    )
    (net (code "142") (name "X_A10") (class "Default")
      (node (ref "IC3") (pin "18") (pinfunction "B0_18") (pintype "bidirectional"))
      (node (ref "U$2") (pin "20") (pinfunction "X1D38_20") (pintype "bidirectional"))
    )
    (net (code "143") (name "X_A11") (class "Default")
      (node (ref "IC3") (pin "16") (pinfunction "B2_16") (pintype "bidirectional"))
      (node (ref "U$2") (pin "21") (pinfunction "X1D39_21") (pintype "bidirectional"))
    )
    (net (code "144") (name "X_A12") (class "Default")
      (node (ref "IC2") (pin "18") (pinfunction "B0_18") (pintype "bidirectional"))
      (node (ref "U$2") (pin "105") (pinfunction "X1D40_105") (pintype "bidirectional"))
    )
    (net (code "145") (name "X_A13") (class "Default")
      (node (ref "IC5") (pin "14") (pinfunction "B4_14") (pintype "bidirectional"))
      (node (ref "U$2") (pin "106") (pinfunction "X1D41_106") (pintype "bidirectional"))
    )
    (net (code "146") (name "X_A14") (class "Default")
      (node (ref "IC5") (pin "16") (pinfunction "B2_16") (pintype "bidirectional"))
      (node (ref "U$2") (pin "107") (pinfunction "X1D42_107") (pintype "bidirectional"))
    )
    (net (code "147") (name "X_A15") (class "Default")
      (node (ref "IC5") (pin "17") (pinfunction "B1_17") (pintype "bidirectional"))
      (node (ref "U$2") (pin "108") (pinfunction "X1D43_108") (pintype "bidirectional"))
    )
    (net (code "148") (name "X_B02") (class "Default")
      (node (ref "IC4") (pin "13") (pinfunction "B5_13") (pintype "bidirectional"))
      (node (ref "U$2") (pin "120") (pinfunction "X1D10_120") (pintype "bidirectional"))
    )
    (net (code "149") (name "X_D0") (class "Default")
      (node (ref "IC3") (pin "13") (pinfunction "B5_13") (pintype "bidirectional"))
      (node (ref "U$2") (pin "71") (pinfunction "X1D02_71") (pintype "bidirectional"))
    )
    (net (code "150") (name "X_D1") (class "Default")
      (node (ref "IC3") (pin "11") (pinfunction "B7_11") (pintype "bidirectional"))
      (node (ref "U$2") (pin "73") (pinfunction "X1D03_73") (pintype "bidirectional"))
    )
    (net (code "151") (name "X_D2") (class "Default")
      (node (ref "IC2") (pin "17") (pinfunction "B1_17") (pintype "bidirectional"))
      (node (ref "U$2") (pin "74") (pinfunction "X1D04_74") (pintype "bidirectional"))
    )
    (net (code "152") (name "X_D3") (class "Default")
      (node (ref "IC3") (pin "12") (pinfunction "B6_12") (pintype "bidirectional"))
      (node (ref "U$2") (pin "75") (pinfunction "X1D05_75") (pintype "bidirectional"))
    )
    (net (code "153") (name "X_D4") (class "Default")
      (node (ref "IC2") (pin "13") (pinfunction "B5_13") (pintype "bidirectional"))
      (node (ref "U$2") (pin "76") (pinfunction "X1D06_76") (pintype "bidirectional"))
    )
    (net (code "154") (name "X_D5") (class "Default")
      (node (ref "IC2") (pin "15") (pinfunction "B3_15") (pintype "bidirectional"))
      (node (ref "U$2") (pin "78") (pinfunction "X1D07_78") (pintype "bidirectional"))
    )
    (net (code "155") (name "X_D6") (class "Default")
      (node (ref "IC3") (pin "15") (pinfunction "B3_15") (pintype "bidirectional"))
      (node (ref "U$2") (pin "81") (pinfunction "X1D08_81") (pintype "bidirectional"))
    )
    (net (code "156") (name "X_D7") (class "Default")
      (node (ref "IC3") (pin "14") (pinfunction "B4_14") (pintype "bidirectional"))
      (node (ref "U$2") (pin "83") (pinfunction "X1D09_83") (pintype "bidirectional"))
    )
    (net (code "157") (name "X_RD4") (class "Default")
      (node (ref "IC1") (pin "11") (pinfunction "B7_11") (pintype "bidirectional"))
      (node (ref "U$2") (pin "45") (pinfunction "X1D13_45") (pintype "bidirectional"))
    )
    (net (code "158") (name "X_RD5") (class "Default")
      (node (ref "IC4") (pin "12") (pinfunction "B6_12") (pintype "bidirectional"))
      (node (ref "U$2") (pin "54") (pinfunction "X1D25_54") (pintype "bidirectional"))
    )
    (net (code "159") (name "X_R{slash}~{W}") (class "Default")
      (node (ref "IC4") (pin "11") (pinfunction "B7_11") (pintype "bidirectional"))
      (node (ref "U$2") (pin "50") (pinfunction "X1D15_50") (pintype "bidirectional"))
    )
    (net (code "160") (name "unconnected-(IC1-NC-Pad1)") (class "Default")
      (node (ref "IC1") (pin "1") (pinfunction "NC_1") (pintype "no_connect"))
    )
    (net (code "161") (name "unconnected-(IC2-NC-Pad1)") (class "Default")
      (node (ref "IC2") (pin "1") (pinfunction "NC_1") (pintype "no_connect"))
    )
    (net (code "162") (name "unconnected-(IC3-NC-Pad1)") (class "Default")
      (node (ref "IC3") (pin "1") (pinfunction "NC_1") (pintype "no_connect"))
    )
    (net (code "163") (name "unconnected-(IC4-NC-Pad1)") (class "Default")
      (node (ref "IC4") (pin "1") (pinfunction "NC_1") (pintype "no_connect"))
    )
    (net (code "164") (name "unconnected-(IC5-A6-Pad8)") (class "Default")
      (node (ref "IC5") (pin "8") (pinfunction "A6_8") (pintype "bidirectional"))
    )
    (net (code "165") (name "unconnected-(IC5-A7-Pad9)") (class "Default")
      (node (ref "IC5") (pin "9") (pinfunction "A7_9") (pintype "bidirectional"))
    )
    (net (code "166") (name "unconnected-(IC5-B6-Pad12)") (class "Default")
      (node (ref "IC5") (pin "12") (pinfunction "B6_12") (pintype "bidirectional"))
    )
    (net (code "167") (name "unconnected-(IC5-B7-Pad11)") (class "Default")
      (node (ref "IC5") (pin "11") (pinfunction "B7_11") (pintype "bidirectional"))
    )
    (net (code "168") (name "unconnected-(IC5-NC-Pad1)") (class "Default")
      (node (ref "IC5") (pin "1") (pinfunction "NC_1") (pintype "no_connect"))
    )
    (net (code "169") (name "unconnected-(U$1-AUDIO-PadP$35)") (class "Default")
      (node (ref "U$1") (pin "P$35") (pinfunction "AUDIO_P$35") (pintype "bidirectional"))
    )
    (net (code "170") (name "unconnected-(U$1-RSRV-PadP$38)") (class "Default")
      (node (ref "U$1") (pin "P$38") (pinfunction "RSRV_P$38") (pintype "bidirectional"))
    )
    (net (code "171") (name "unconnected-(U$2A-NC-Pad65)") (class "Default")
      (node (ref "U$2") (pin "65") (pinfunction "NC_65") (pintype "bidirectional"))
    )
    (net (code "172") (name "unconnected-(U$2C-X0D11-Pad33)") (class "Default")
      (node (ref "U$2") (pin "33") (pinfunction "X0D11_33") (pintype "bidirectional"))
    )
    (net (code "173") (name "unconnected-(U$2C-X0D12-Pad61)") (class "Default")
      (node (ref "U$2") (pin "61") (pinfunction "X0D12_61") (pintype "bidirectional"))
    )
    (net (code "174") (name "unconnected-(U$2C-X0D13-Pad62)") (class "Default")
      (node (ref "U$2") (pin "62") (pinfunction "X0D13_62") (pintype "bidirectional"))
    )
    (net (code "175") (name "unconnected-(U$2D-X1D00-Pad84)") (class "Default")
      (node (ref "U$2") (pin "84") (pinfunction "X1D00_84") (pintype "bidirectional"))
    )
    (net (code "176") (name "unconnected-(U$2D-X1D18-Pad25)") (class "Default")
      (node (ref "U$2") (pin "25") (pinfunction "X1D18_25") (pintype "bidirectional"))
    )
    (net (code "177") (name "unconnected-(U$2D-X1D19-Pad26)") (class "Default")
      (node (ref "U$2") (pin "26") (pinfunction "X1D19_26") (pintype "bidirectional"))
    )
    (net (code "178") (name "unconnected-(U$2D-X1D34-Pad12)") (class "Default")
      (node (ref "U$2") (pin "12") (pinfunction "X1D34_12") (pintype "bidirectional"))
    )
    (net (code "179") (name "unconnected-(U$2D-X1D35-Pad14)") (class "Default")
      (node (ref "U$2") (pin "14") (pinfunction "X1D35_14") (pintype "bidirectional"))
    )
    (net (code "180") (name "unconnected-(U$3-NC-Pad1)") (class "Default")
      (node (ref "U$3") (pin "1") (pinfunction "NC_1") (pintype "bidirectional"))
    )
    (net (code "181") (name "unconnected-(U$6-~{MR}-Pad3)") (class "Default")
      (node (ref "U$6") (pin "3") (pinfunction "~{MR}_3") (pintype "bidirectional"))
    )
    (net (code "182") (name "unconnected-(U$7-NC-Pad40)") (class "Default")
      (node (ref "U$7") (pin "40") (pinfunction "NC_40") (pintype "bidirectional"))
    )
    (net (code "183") (name "unconnected-(U1-EN-Pad1)") (class "Default")
      (node (ref "U1") (pin "1") (pinfunction "EN_1") (pintype "bidirectional"))
    )
    (net (code "184") (name "unconnected-(USBPOWER-Pad2)") (class "Default")
      (node (ref "USBPOWER") (pin "2") (pinfunction "2_2") (pintype "input"))
    )
    (net (code "185") (name "unconnected-(USBPOWER-Pad3)") (class "Default")
      (node (ref "USBPOWER") (pin "3") (pinfunction "3_3") (pintype "input"))
    )
    (net (code "186") (name "unconnected-(USBPOWER-Pad4)") (class "Default")
      (node (ref "USBPOWER") (pin "4") (pinfunction "4_4") (pintype "input"))
    )
    (net (code "187") (name "unconnected-(XTAG-Pad1)") (class "Default")
      (node (ref "XTAG") (pin "1") (pinfunction "1_1") (pintype "passive"))
    )
    (net (code "188") (name "unconnected-(XTAG-Pad2)") (class "Default")
      (node (ref "XTAG") (pin "2") (pinfunction "2_2") (pintype "passive"))
    )
    (net (code "189") (name "unconnected-(XTAG-Pad3)") (class "Default")
      (node (ref "XTAG") (pin "3") (pinfunction "3_3") (pintype "passive"))
    )
    (net (code "190") (name "unconnected-(XTAG-Pad11)") (class "Default")
      (node (ref "XTAG") (pin "11") (pinfunction "11_11") (pintype "passive"))
    )
    (net (code "191") (name "unconnected-(XTAG-Pad17)") (class "Default")
      (node (ref "XTAG") (pin "17") (pinfunction "17_17") (pintype "passive"))
    )
    (net (code "192") (name "unconnected-(XTAG-Pad19)") (class "Default")
      (node (ref "XTAG") (pin "19") (pinfunction "19_19") (pintype "passive"))
    )
    (net (code "193") (name "~{QSPI_CS}") (class "Default")
      (node (ref "R11") (pin "2") (pinfunction "2_2") (pintype "passive"))
      (node (ref "U$10") (pin "1") (pinfunction "~{CS}_1") (pintype "bidirectional"))
      (node (ref "U$2") (pin "27") (pinfunction "X0D01_27") (pintype "bidirectional"))
    )
    (net (code "194") (name "~{RESET}") (class "Default")
      (node (ref "R14") (pin "1") (pinfunction "1_1") (pintype "passive"))
      (node (ref "U$11") (pin "1") (pinfunction "~{RESET}_1") (pintype "bidirectional"))
      (node (ref "U$2") (pin "122") (pinfunction "TRST_N_122") (pintype "bidirectional"))
      (node (ref "U$2") (pin "123") (pinfunction "RST_N_123") (pintype "bidirectional"))
      (node (ref "U$3") (pin "4") (pinfunction "Y_4") (pintype "bidirectional"))
    )
    (net (code "195") (name "~{SD_CAS}") (class "Default")
      (node (ref "U$2") (pin "90") (pinfunction "X0D35_90") (pintype "bidirectional"))
      (node (ref "U$7") (pin "17") (pinfunction "~{CAS}_17") (pintype "bidirectional"))
      (node (ref "U$8") (pin "1") (pinfunction "I0_1") (pintype "input"))
    )
    (net (code "196") (name "~{SD_ENABLE}") (class "Default")
      (node (ref "R10") (pin "2") (pinfunction "2_2") (pintype "passive"))
      (node (ref "U$2") (pin "32") (pinfunction "X0D00_32") (pintype "bidirectional"))
      (node (ref "U$9") (pin "1") (pinfunction "S_1") (pintype "bidirectional"))
    )
    (net (code "197") (name "~{SD_RAS}") (class "Default")
      (node (ref "U$2") (pin "2") (pinfunction "X0D36_2") (pintype "bidirectional"))
      (node (ref "U$7") (pin "18") (pinfunction "~{RAS}_18") (pintype "bidirectional"))
    )
    (net (code "198") (name "~{SD_WE}") (class "Default")
      (node (ref "U$2") (pin "3") (pinfunction "X0D37_3") (pintype "bidirectional"))
      (node (ref "U$7") (pin "16") (pinfunction "~{WE}_16") (pintype "bidirectional"))
      (node (ref "U$8") (pin "2") (pinfunction "I1_2") (pintype "input"))
    )
    (net (code "199") (name "~{X_CCTL}") (class "Default")
      (node (ref "IC4") (pin "14") (pinfunction "B4_14") (pintype "bidirectional"))
      (node (ref "U$2") (pin "53") (pinfunction "X1D24_53") (pintype "bidirectional"))
    )
    (net (code "200") (name "~{X_D1XX}") (class "Default")
      (node (ref "IC5") (pin "13") (pinfunction "B5_13") (pintype "bidirectional"))
      (node (ref "U$2") (pin "51") (pinfunction "X1D20_51") (pintype "bidirectional"))
    )
    (net (code "201") (name "~{X_EXSEL}") (class "Default")
      (node (ref "IC4") (pin "15") (pinfunction "B3_15") (pintype "bidirectional"))
      (node (ref "U$2") (pin "23") (pinfunction "X1D17_23") (pintype "bidirectional"))
    )
    (net (code "202") (name "~{X_HALT}") (class "Default")
      (node (ref "IC4") (pin "18") (pinfunction "B0_18") (pintype "bidirectional"))
      (node (ref "U$2") (pin "31") (pinfunction "X1D23_31") (pintype "bidirectional"))
    )
    (net (code "203") (name "~{X_IRQ}") (class "Default")
      (node (ref "IC4") (pin "16") (pinfunction "B2_16") (pintype "bidirectional"))
      (node (ref "U$2") (pin "121") (pinfunction "X1D11_121") (pintype "bidirectional"))
    )
    (net (code "204") (name "~{X_MPD}") (class "Default")
      (node (ref "IC5") (pin "15") (pinfunction "B3_15") (pintype "bidirectional"))
      (node (ref "U$2") (pin "22") (pinfunction "X1D16_22") (pintype "bidirectional"))
    )
    (net (code "205") (name "~{X_REF}") (class "Default")
      (node (ref "IC5") (pin "18") (pinfunction "B0_18") (pintype "bidirectional"))
      (node (ref "U$2") (pin "52") (pinfunction "X1D21_52") (pintype "bidirectional"))
    )
    (net (code "206") (name "~{X_RST}") (class "Default")
      (node (ref "IC4") (pin "17") (pinfunction "B1_17") (pintype "bidirectional"))
      (node (ref "U$2") (pin "49") (pinfunction "X1D14_49") (pintype "bidirectional"))
    )
    (net (code "207") (name "~{X_S4}") (class "Default")
      (node (ref "IC1") (pin "12") (pinfunction "B6_12") (pintype "bidirectional"))
      (node (ref "U$2") (pin "44") (pinfunction "X1D12_44") (pintype "bidirectional"))
    )
    (net (code "208") (name "~{X_S5}") (class "Default")
      (node (ref "IC3") (pin "17") (pinfunction "B1_17") (pintype "bidirectional"))
      (node (ref "U$2") (pin "30") (pinfunction "X1D22_30") (pintype "bidirectional"))
    )
  )
)
